# omicron2.net
KiCad netlist of a schematic drawn in EAGLE
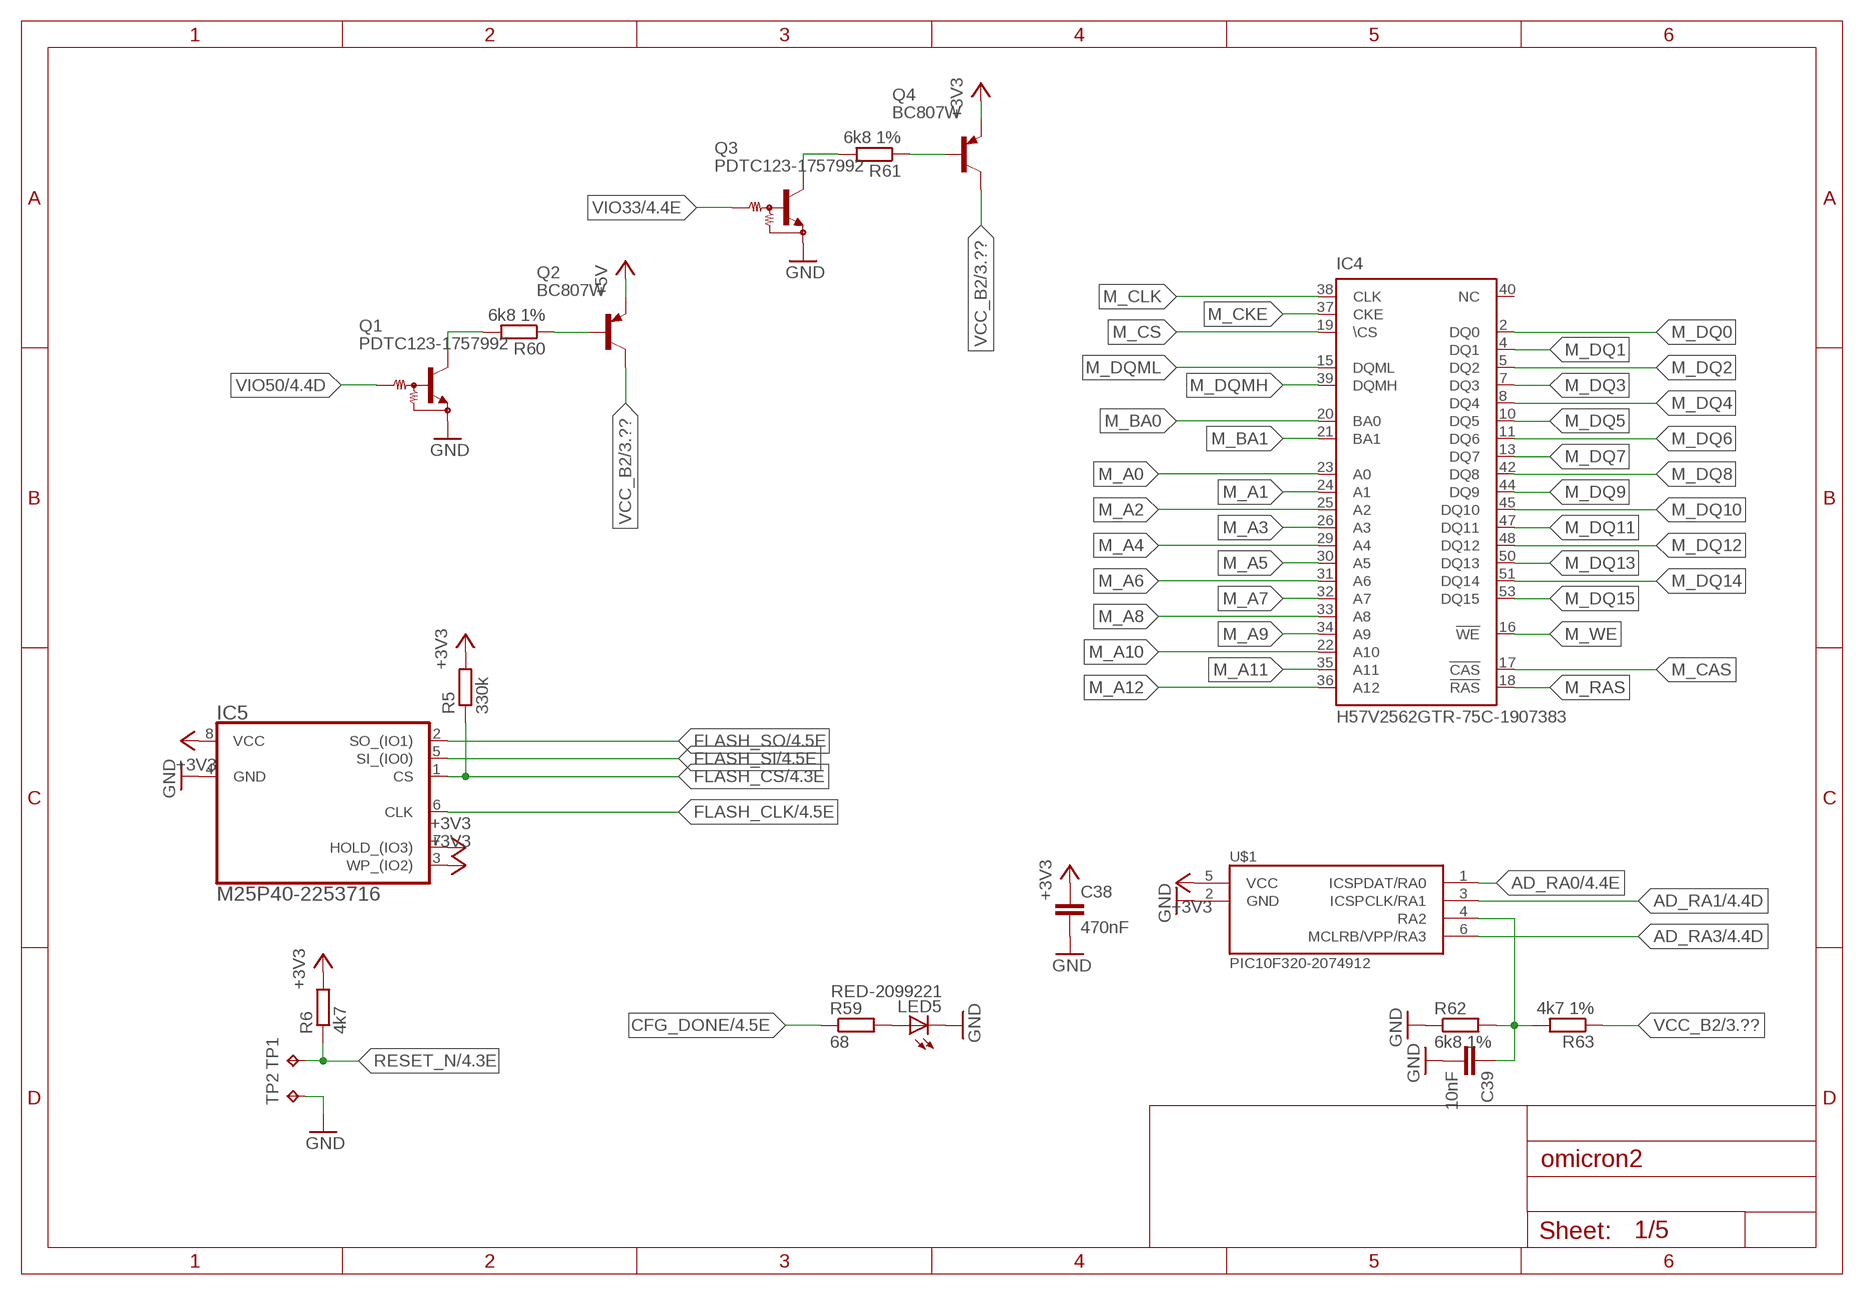
[diagram p0: schematic, sheet 1]
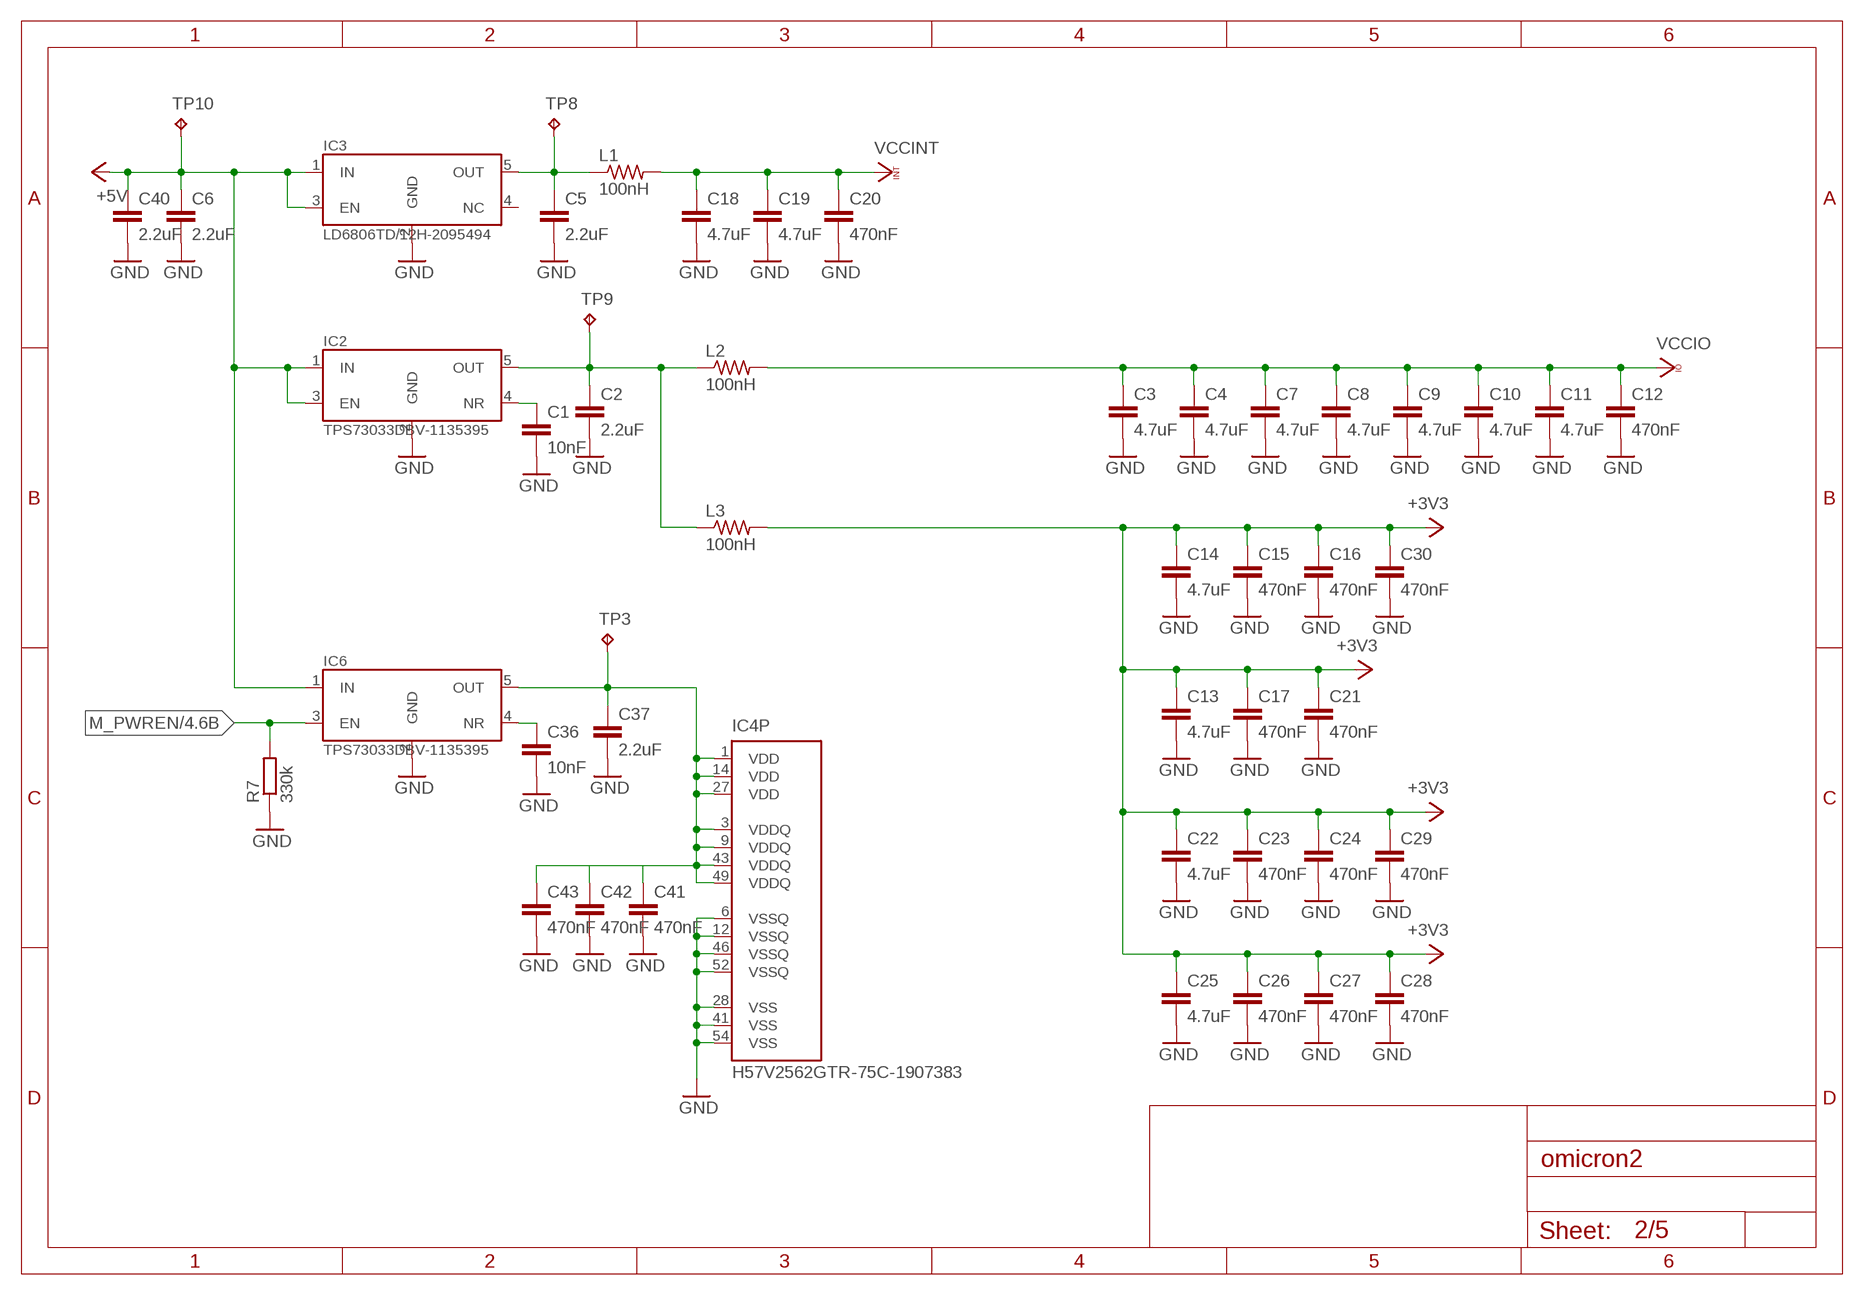
[diagram p1: schematic, sheet 2]
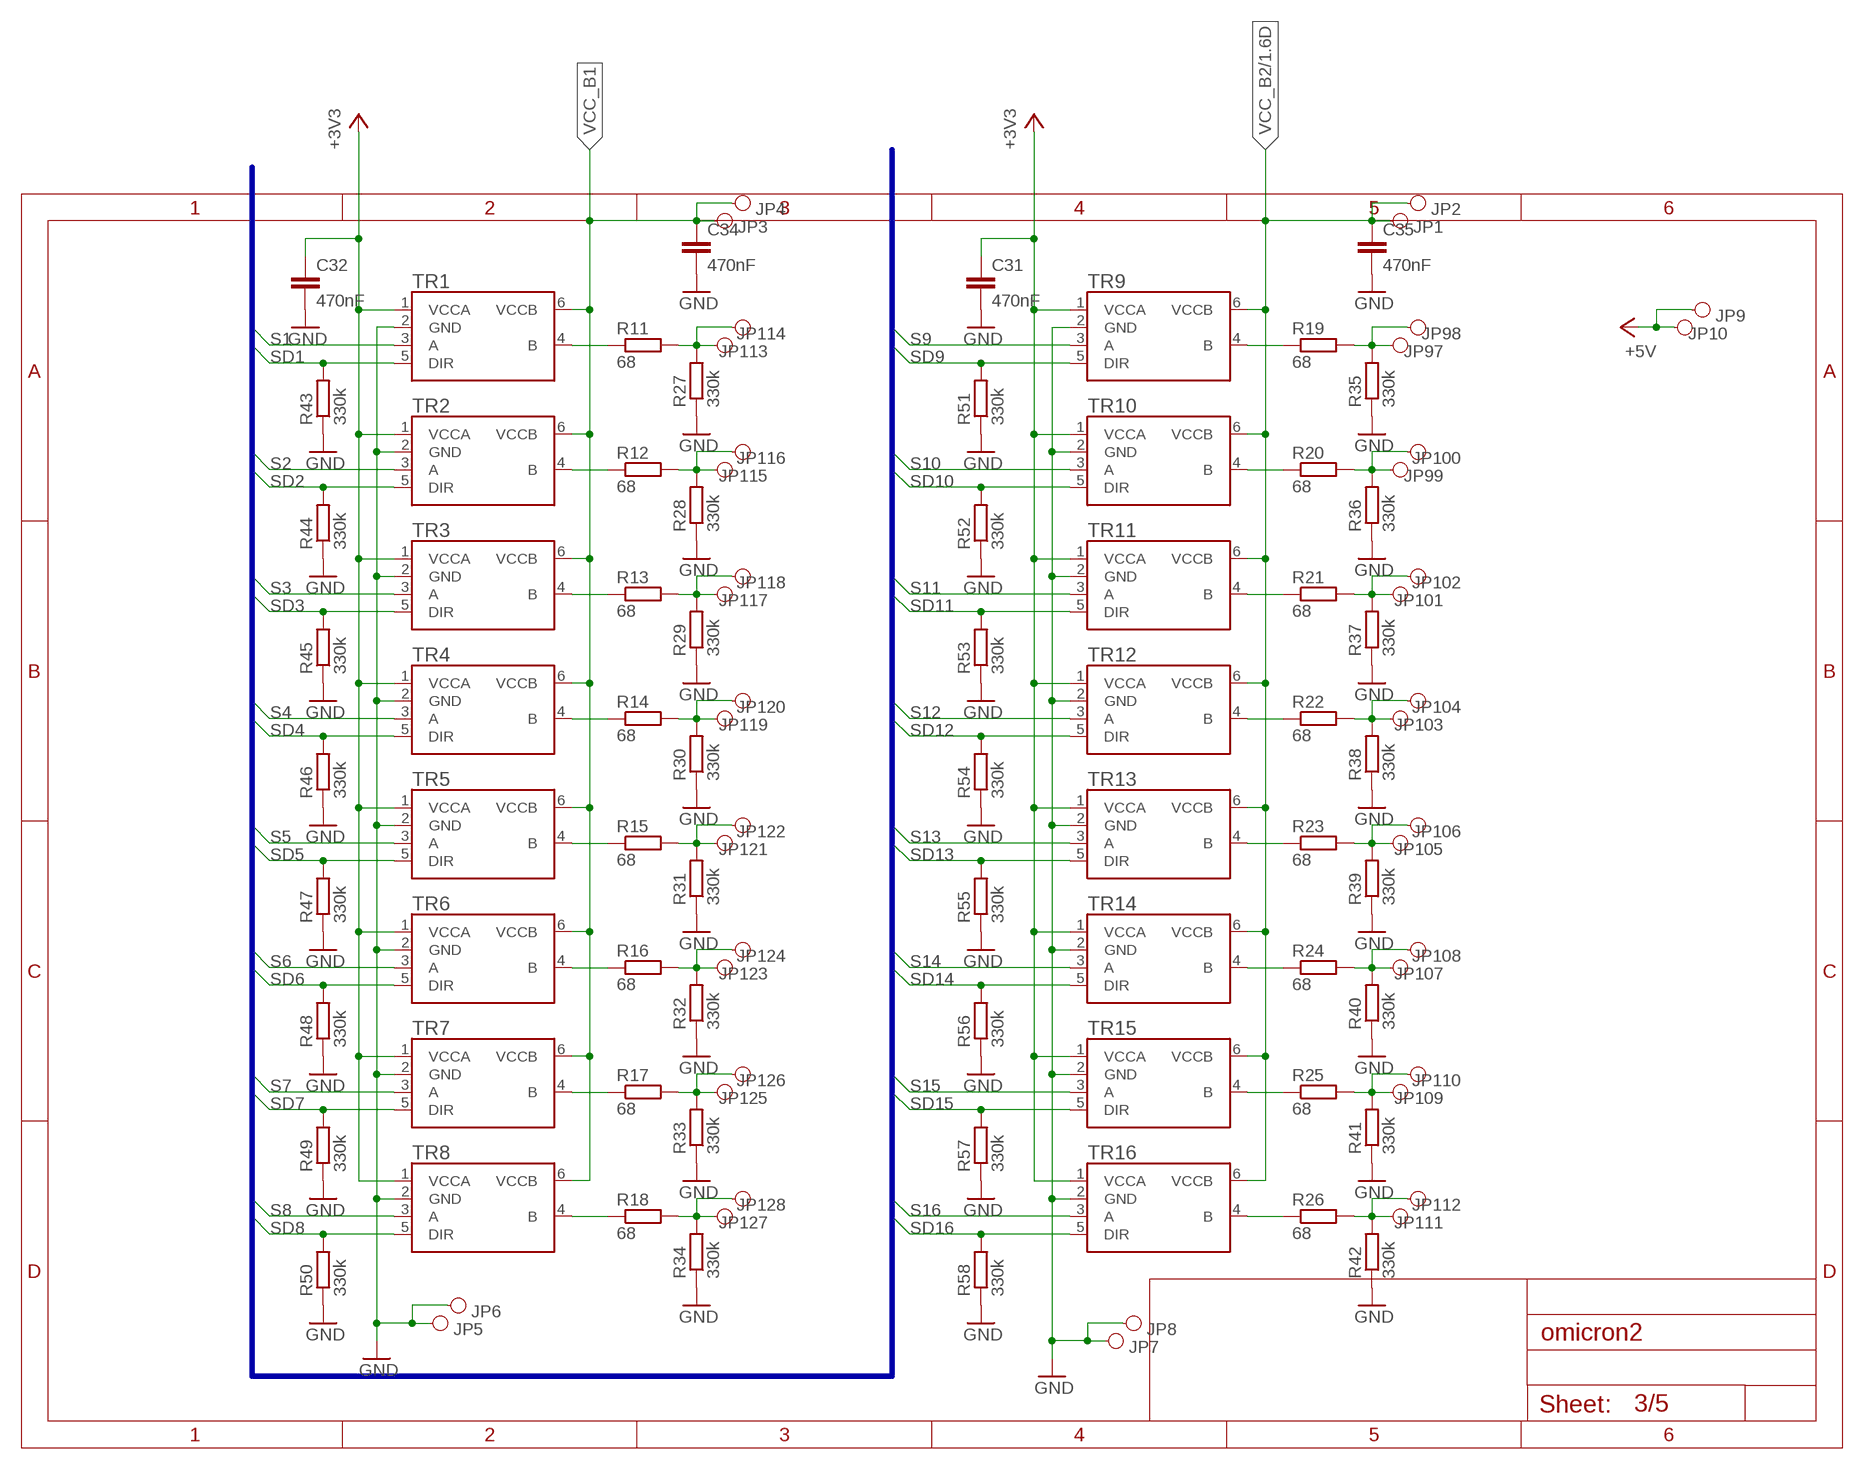
[diagram p2: schematic, sheet 3]
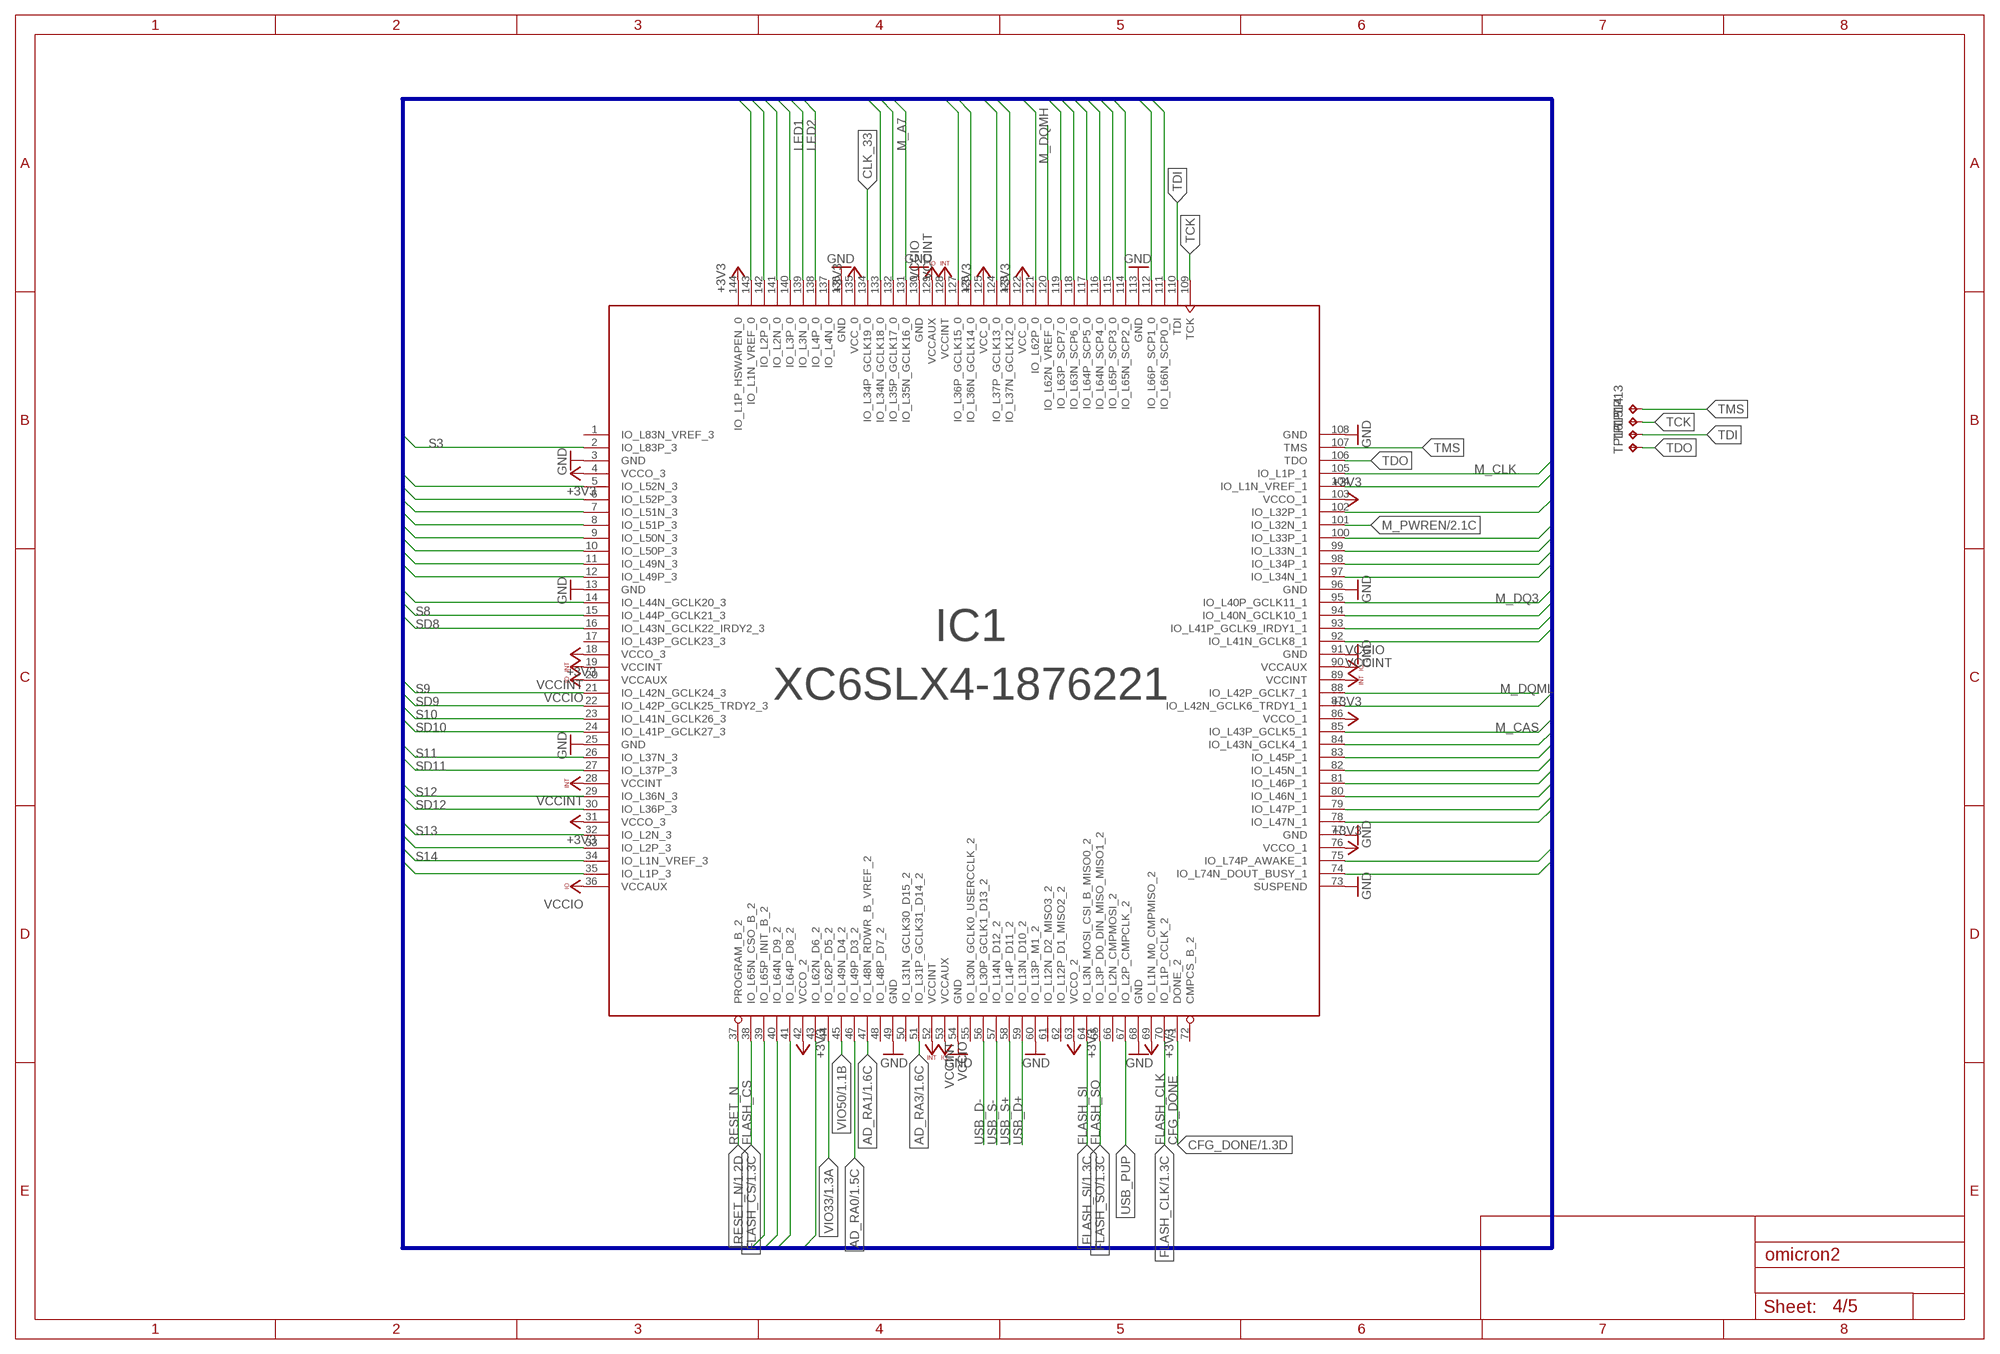
[diagram p3: schematic, sheet 4]
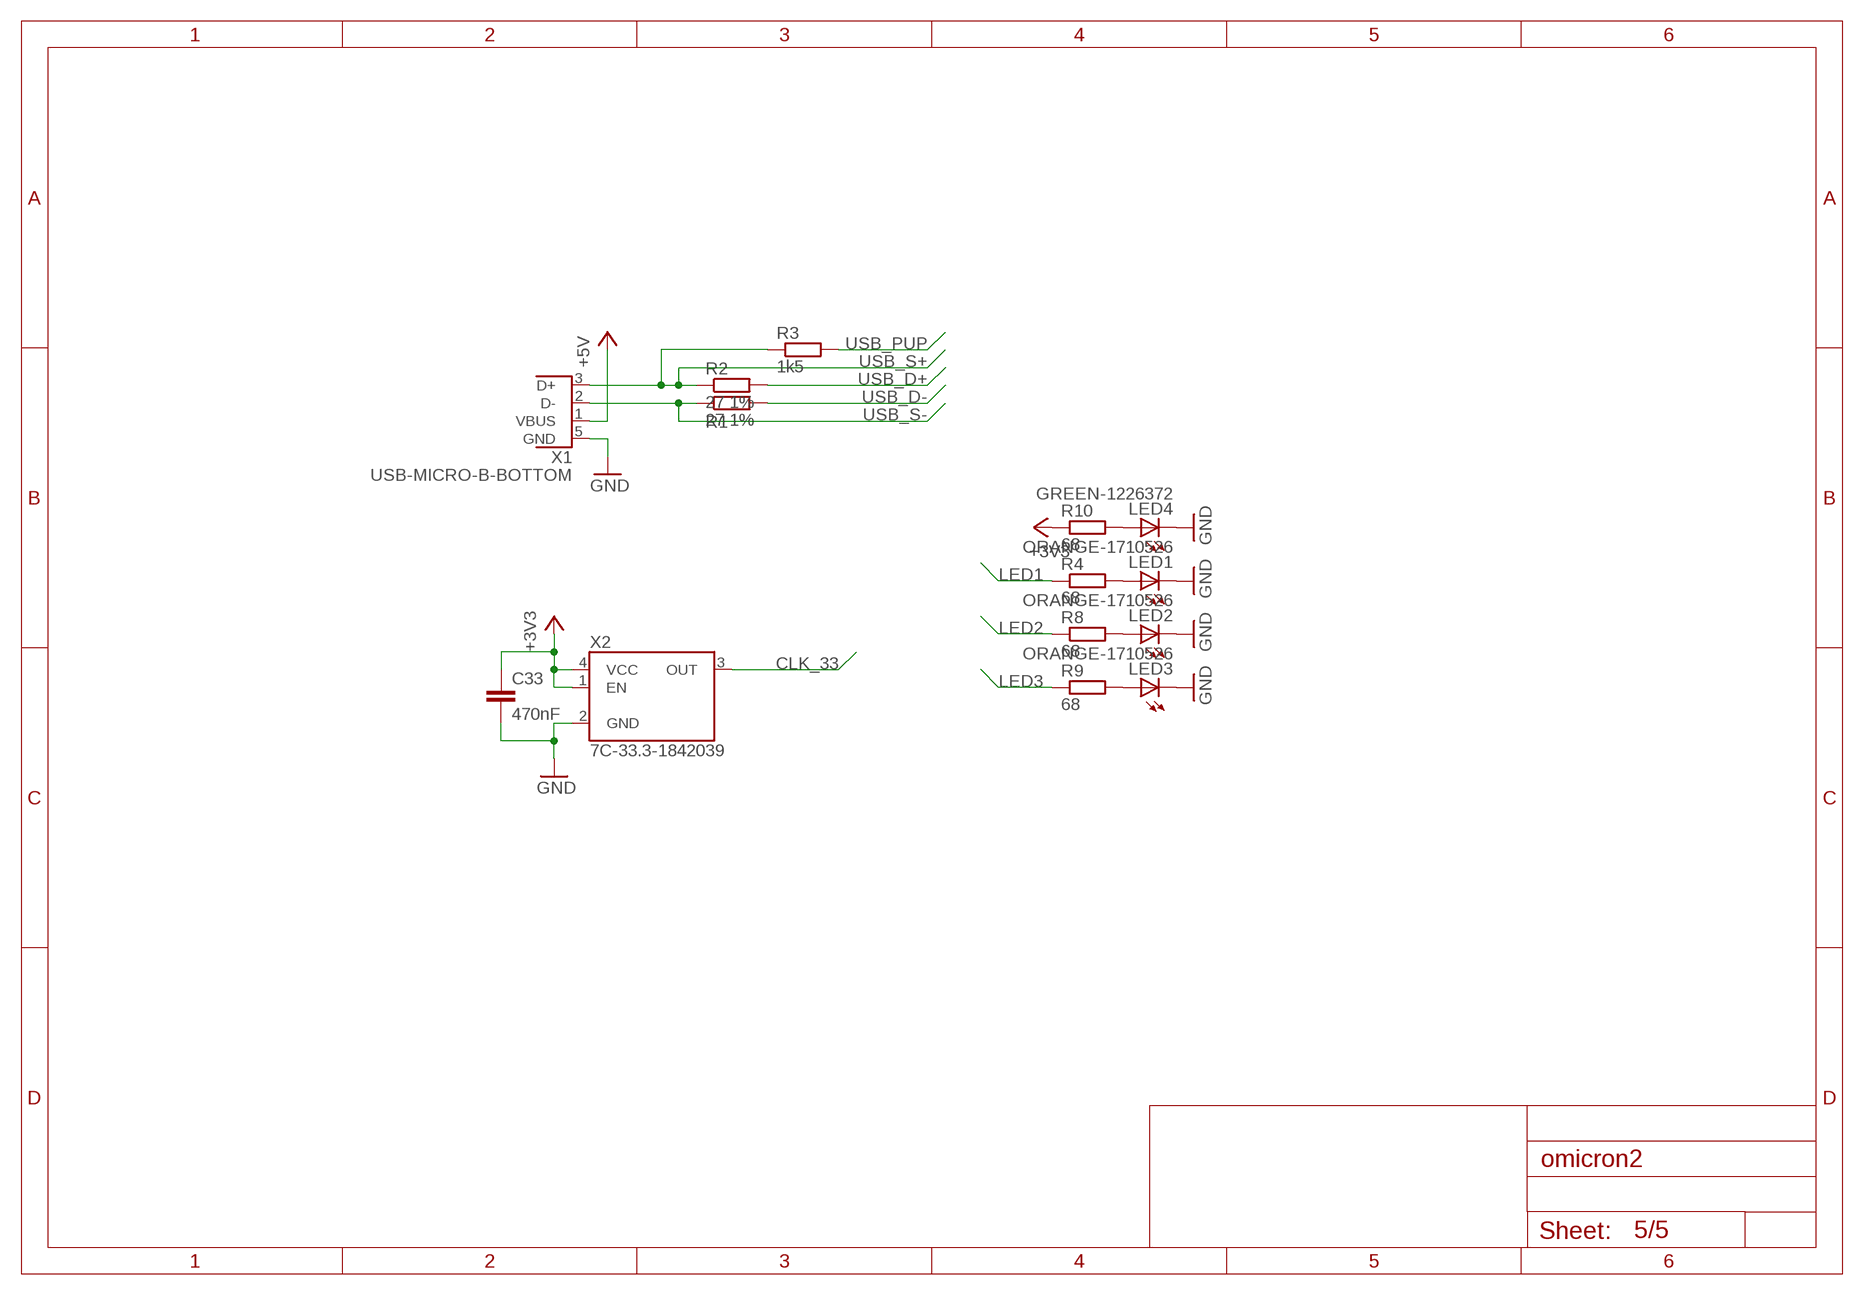
[diagram p4: schematic, sheet 5]

(export (version "E")
  (design (tool "Eeschema 10.0.6"))
  (components
    (comp (ref "C38")
      (value "470nF")
      (footprint "eagle-import:C0603")
      (libsource (lib "eagle-import") (part "C-EUC0603"))
    )
    (comp (ref "C39")
      (value "10nF")
      (footprint "eagle-import:C0603")
      (libsource (lib "eagle-import") (part "C-EUC0603"))
    )
    (comp (ref "IC4")
      (value "H57V2562GTR-75C-1907383")
      (footprint "eagle-import:TSOP54-400")
      (libsource (lib "eagle-import") (part "MT48LC64M4A2"))
    )
    (comp (ref "IC5")
      (value "M25P40-2253716")
      (footprint "eagle-import:SO8")
      (libsource (lib "eagle-import") (part "FLASH"))
    )
    (comp (ref "LED5")
      (value "RED-2099221")
      (footprint "eagle-import:CHIPLED_0603")
      (libsource (lib "eagle-import") (part "LEDCHIPLED_0603"))
    )
    (comp (ref "Q1")
      (value "PDTC123-1757992")
      (footprint "eagle-import:SOT323")
      (libsource (lib "eagle-import") (part "NPN-BIAS-SOT323-BEC"))
    )
    (comp (ref "Q2")
      (value "BC807W")
      (footprint "eagle-import:SOT323-BEC")
      (libsource (lib "eagle-import") (part "BC807W"))
    )
    (comp (ref "Q3")
      (value "PDTC123-1757992")
      (footprint "eagle-import:SOT323")
      (libsource (lib "eagle-import") (part "NPN-BIAS-SOT323-BEC"))
    )
    (comp (ref "Q4")
      (value "BC807W")
      (footprint "eagle-import:SOT323-BEC")
      (libsource (lib "eagle-import") (part "BC807W"))
    )
    (comp (ref "R5")
      (value "330k")
      (footprint "eagle-import:R0603")
      (libsource (lib "eagle-import") (part "R-EU_R0603"))
    )
    (comp (ref "R6")
      (value "4k7")
      (footprint "eagle-import:R0603")
      (libsource (lib "eagle-import") (part "R-EU_R0603"))
    )
    (comp (ref "R59")
      (value "68")
      (footprint "eagle-import:R0603")
      (libsource (lib "eagle-import") (part "R-EU_R0603"))
    )
    (comp (ref "R60")
      (value "6k8 1%")
      (footprint "eagle-import:R0603")
      (libsource (lib "eagle-import") (part "R-EU_R0603"))
    )
    (comp (ref "R61")
      (value "6k8 1%")
      (footprint "eagle-import:R0603")
      (libsource (lib "eagle-import") (part "R-EU_R0603"))
    )
    (comp (ref "R62")
      (value "6k8 1%")
      (footprint "eagle-import:R0603")
      (libsource (lib "eagle-import") (part "R-EU_R0603"))
    )
    (comp (ref "R63")
      (value "4k7 1%")
      (footprint "eagle-import:R0603")
      (libsource (lib "eagle-import") (part "R-EU_R0603"))
    )
    (comp (ref "TP1")
      (value "TPTP15R")
      (footprint "eagle-import:TP15R")
      (libsource (lib "eagle-import") (part "TPTP15R"))
    )
    (comp (ref "TP2")
      (value "TPTP20R")
      (footprint "eagle-import:TP20R")
      (libsource (lib "eagle-import") (part "TPTP20R"))
    )
    (comp (ref "U$1")
      (value "PIC10F320-2074912")
      (footprint "eagle-import:SOT23")
      (libsource (lib "eagle-import") (part "PIC10F320"))
    )
    (comp (ref "C33")
      (value "470nF")
      (footprint "eagle-import:C0603")
      (libsource (lib "eagle-import") (part "C-EUC0603"))
    )
    (comp (ref "LED1")
      (value "ORANGE-1710526")
      (footprint "eagle-import:CHIPLED_0603")
      (libsource (lib "eagle-import") (part "LEDCHIPLED_0603"))
    )
    (comp (ref "LED2")
      (value "ORANGE-1710526")
      (footprint "eagle-import:CHIPLED_0603")
      (libsource (lib "eagle-import") (part "LEDCHIPLED_0603"))
    )
    (comp (ref "LED3")
      (value "ORANGE-1710526")
      (footprint "eagle-import:CHIPLED_0603")
      (libsource (lib "eagle-import") (part "LEDCHIPLED_0603"))
    )
    (comp (ref "LED4")
      (value "GREEN-1226372")
      (footprint "eagle-import:CHIPLED_0603")
      (libsource (lib "eagle-import") (part "LEDCHIPLED_0603"))
    )
    (comp (ref "R1")
      (value "27 1%")
      (footprint "eagle-import:R0603")
      (libsource (lib "eagle-import") (part "R-EU_R0603"))
    )
    (comp (ref "R2")
      (value "27 1%")
      (footprint "eagle-import:R0603")
      (libsource (lib "eagle-import") (part "R-EU_R0603"))
    )
    (comp (ref "R3")
      (value "1k5")
      (footprint "eagle-import:R0603")
      (libsource (lib "eagle-import") (part "R-EU_R0603"))
    )
    (comp (ref "R4")
      (value "68")
      (footprint "eagle-import:R0603")
      (libsource (lib "eagle-import") (part "R-EU_R0603"))
    )
    (comp (ref "R8")
      (value "68")
      (footprint "eagle-import:R0603")
      (libsource (lib "eagle-import") (part "R-EU_R0603"))
    )
    (comp (ref "R9")
      (value "68")
      (footprint "eagle-import:R0603")
      (libsource (lib "eagle-import") (part "R-EU_R0603"))
    )
    (comp (ref "R10")
      (value "68")
      (footprint "eagle-import:R0603")
      (libsource (lib "eagle-import") (part "R-EU_R0603"))
    )
    (comp (ref "X1")
      (value "USB-MICRO-B-BOTTOM")
      (footprint "eagle-import:USB-MICRO-B-BOTTOM-MOLEX")
      (libsource (lib "eagle-import") (part "USB-MICRO-B-BOTTOM"))
    )
    (comp (ref "X2")
      (value "7C-33.3-1842039")
      (footprint "eagle-import:5X3.2_HAND")
      (libsource (lib "eagle-import") (part "OSC-5X3.2HS"))
    )
    (comp (ref "C31")
      (value "470nF")
      (footprint "eagle-import:C0603")
      (libsource (lib "eagle-import") (part "C-EUC0603"))
    )
    (comp (ref "C32")
      (value "470nF")
      (footprint "eagle-import:C0603")
      (libsource (lib "eagle-import") (part "C-EUC0603"))
    )
    (comp (ref "C34")
      (value "470nF")
      (footprint "eagle-import:C0603")
      (libsource (lib "eagle-import") (part "C-EUC0603"))
    )
    (comp (ref "C35")
      (value "470nF")
      (footprint "eagle-import:C0603")
      (libsource (lib "eagle-import") (part "C-EUC0603"))
    )
    (comp (ref "JP1")
      (value "PINH1X01SMD")
      (footprint "eagle-import:PINH1X01SMD")
      (libsource (lib "eagle-import") (part "PINH1X01SMD"))
    )
    (comp (ref "JP2")
      (value "PINH1X01SMD")
      (footprint "eagle-import:PINH1X01SMD")
      (libsource (lib "eagle-import") (part "PINH1X01SMD"))
    )
    (comp (ref "JP3")
      (value "PINH1X01SMD")
      (footprint "eagle-import:PINH1X01SMD")
      (libsource (lib "eagle-import") (part "PINH1X01SMD"))
    )
    (comp (ref "JP4")
      (value "PINH1X01SMD")
      (footprint "eagle-import:PINH1X01SMD")
      (libsource (lib "eagle-import") (part "PINH1X01SMD"))
    )
    (comp (ref "JP5")
      (value "PINH1X01SMD")
      (footprint "eagle-import:PINH1X01SMD")
      (libsource (lib "eagle-import") (part "PINH1X01SMD"))
    )
    (comp (ref "JP6")
      (value "PINH1X01SMD")
      (footprint "eagle-import:PINH1X01SMD")
      (libsource (lib "eagle-import") (part "PINH1X01SMD"))
    )
    (comp (ref "JP7")
      (value "PINH1X01SMD")
      (footprint "eagle-import:PINH1X01SMD")
      (libsource (lib "eagle-import") (part "PINH1X01SMD"))
    )
    (comp (ref "JP8")
      (value "PINH1X01SMD")
      (footprint "eagle-import:PINH1X01SMD")
      (libsource (lib "eagle-import") (part "PINH1X01SMD"))
    )
    (comp (ref "JP9")
      (value "PINH1X01SMD")
      (footprint "eagle-import:PINH1X01SMD")
      (libsource (lib "eagle-import") (part "PINH1X01SMD"))
    )
    (comp (ref "JP10")
      (value "PINH1X01SMD")
      (footprint "eagle-import:PINH1X01SMD")
      (libsource (lib "eagle-import") (part "PINH1X01SMD"))
    )
    (comp (ref "JP97")
      (value "PINH1X01SMD")
      (footprint "eagle-import:PINH1X01SMD")
      (libsource (lib "eagle-import") (part "PINH1X01SMD"))
    )
    (comp (ref "JP98")
      (value "PINH1X01SMD")
      (footprint "eagle-import:PINH1X01SMD")
      (libsource (lib "eagle-import") (part "PINH1X01SMD"))
    )
    (comp (ref "JP99")
      (value "PINH1X01SMD")
      (footprint "eagle-import:PINH1X01SMD")
      (libsource (lib "eagle-import") (part "PINH1X01SMD"))
    )
    (comp (ref "JP100")
      (value "PINH1X01SMD")
      (footprint "eagle-import:PINH1X01SMD")
      (libsource (lib "eagle-import") (part "PINH1X01SMD"))
    )
    (comp (ref "JP101")
      (value "PINH1X01SMD")
      (footprint "eagle-import:PINH1X01SMD")
      (libsource (lib "eagle-import") (part "PINH1X01SMD"))
    )
    (comp (ref "JP102")
      (value "PINH1X01SMD")
      (footprint "eagle-import:PINH1X01SMD")
      (libsource (lib "eagle-import") (part "PINH1X01SMD"))
    )
    (comp (ref "JP103")
      (value "PINH1X01SMD")
      (footprint "eagle-import:PINH1X01SMD")
      (libsource (lib "eagle-import") (part "PINH1X01SMD"))
    )
    (comp (ref "JP104")
      (value "PINH1X01SMD")
      (footprint "eagle-import:PINH1X01SMD")
      (libsource (lib "eagle-import") (part "PINH1X01SMD"))
    )
    (comp (ref "JP105")
      (value "PINH1X01SMD")
      (footprint "eagle-import:PINH1X01SMD")
      (libsource (lib "eagle-import") (part "PINH1X01SMD"))
    )
    (comp (ref "JP106")
      (value "PINH1X01SMD")
      (footprint "eagle-import:PINH1X01SMD")
      (libsource (lib "eagle-import") (part "PINH1X01SMD"))
    )
    (comp (ref "JP107")
      (value "PINH1X01SMD")
      (footprint "eagle-import:PINH1X01SMD")
      (libsource (lib "eagle-import") (part "PINH1X01SMD"))
    )
    (comp (ref "JP108")
      (value "PINH1X01SMD")
      (footprint "eagle-import:PINH1X01SMD")
      (libsource (lib "eagle-import") (part "PINH1X01SMD"))
    )
    (comp (ref "JP109")
      (value "PINH1X01SMD")
      (footprint "eagle-import:PINH1X01SMD")
      (libsource (lib "eagle-import") (part "PINH1X01SMD"))
    )
    (comp (ref "JP110")
      (value "PINH1X01SMD")
      (footprint "eagle-import:PINH1X01SMD")
      (libsource (lib "eagle-import") (part "PINH1X01SMD"))
    )
    (comp (ref "JP111")
      (value "PINH1X01SMD")
      (footprint "eagle-import:PINH1X01SMD")
      (libsource (lib "eagle-import") (part "PINH1X01SMD"))
    )
    (comp (ref "JP112")
      (value "PINH1X01SMD")
      (footprint "eagle-import:PINH1X01SMD")
      (libsource (lib "eagle-import") (part "PINH1X01SMD"))
    )
    (comp (ref "JP113")
      (value "PINH1X01SMD")
      (footprint "eagle-import:PINH1X01SMD")
      (libsource (lib "eagle-import") (part "PINH1X01SMD"))
    )
    (comp (ref "JP114")
      (value "PINH1X01SMD")
      (footprint "eagle-import:PINH1X01SMD")
      (libsource (lib "eagle-import") (part "PINH1X01SMD"))
    )
    (comp (ref "JP115")
      (value "PINH1X01SMD")
      (footprint "eagle-import:PINH1X01SMD")
      (libsource (lib "eagle-import") (part "PINH1X01SMD"))
    )
    (comp (ref "JP116")
      (value "PINH1X01SMD")
      (footprint "eagle-import:PINH1X01SMD")
      (libsource (lib "eagle-import") (part "PINH1X01SMD"))
    )
    (comp (ref "JP117")
      (value "PINH1X01SMD")
      (footprint "eagle-import:PINH1X01SMD")
      (libsource (lib "eagle-import") (part "PINH1X01SMD"))
    )
    (comp (ref "JP118")
      (value "PINH1X01SMD")
      (footprint "eagle-import:PINH1X01SMD")
      (libsource (lib "eagle-import") (part "PINH1X01SMD"))
    )
    (comp (ref "JP119")
      (value "PINH1X01SMD")
      (footprint "eagle-import:PINH1X01SMD")
      (libsource (lib "eagle-import") (part "PINH1X01SMD"))
    )
    (comp (ref "JP120")
      (value "PINH1X01SMD")
      (footprint "eagle-import:PINH1X01SMD")
      (libsource (lib "eagle-import") (part "PINH1X01SMD"))
    )
    (comp (ref "JP121")
      (value "PINH1X01SMD")
      (footprint "eagle-import:PINH1X01SMD")
      (libsource (lib "eagle-import") (part "PINH1X01SMD"))
    )
    (comp (ref "JP122")
      (value "PINH1X01SMD")
      (footprint "eagle-import:PINH1X01SMD")
      (libsource (lib "eagle-import") (part "PINH1X01SMD"))
    )
    (comp (ref "JP123")
      (value "PINH1X01SMD")
      (footprint "eagle-import:PINH1X01SMD")
      (libsource (lib "eagle-import") (part "PINH1X01SMD"))
    )
    (comp (ref "JP124")
      (value "PINH1X01SMD")
      (footprint "eagle-import:PINH1X01SMD")
      (libsource (lib "eagle-import") (part "PINH1X01SMD"))
    )
    (comp (ref "JP125")
      (value "PINH1X01SMD")
      (footprint "eagle-import:PINH1X01SMD")
      (libsource (lib "eagle-import") (part "PINH1X01SMD"))
    )
    (comp (ref "JP126")
      (value "PINH1X01SMD")
      (footprint "eagle-import:PINH1X01SMD")
      (libsource (lib "eagle-import") (part "PINH1X01SMD"))
    )
    (comp (ref "JP127")
      (value "PINH1X01SMD")
      (footprint "eagle-import:PINH1X01SMD")
      (libsource (lib "eagle-import") (part "PINH1X01SMD"))
    )
    (comp (ref "JP128")
      (value "PINH1X01SMD")
      (footprint "eagle-import:PINH1X01SMD")
      (libsource (lib "eagle-import") (part "PINH1X01SMD"))
    )
    (comp (ref "R11")
      (value "68")
      (footprint "eagle-import:R0603")
      (libsource (lib "eagle-import") (part "R-EU_R0603"))
    )
    (comp (ref "R12")
      (value "68")
      (footprint "eagle-import:R0603")
      (libsource (lib "eagle-import") (part "R-EU_R0603"))
    )
    (comp (ref "R13")
      (value "68")
      (footprint "eagle-import:R0603")
      (libsource (lib "eagle-import") (part "R-EU_R0603"))
    )
    (comp (ref "R14")
      (value "68")
      (footprint "eagle-import:R0603")
      (libsource (lib "eagle-import") (part "R-EU_R0603"))
    )
    (comp (ref "R15")
      (value "68")
      (footprint "eagle-import:R0603")
      (libsource (lib "eagle-import") (part "R-EU_R0603"))
    )
    (comp (ref "R16")
      (value "68")
      (footprint "eagle-import:R0603")
      (libsource (lib "eagle-import") (part "R-EU_R0603"))
    )
    (comp (ref "R17")
      (value "68")
      (footprint "eagle-import:R0603")
      (libsource (lib "eagle-import") (part "R-EU_R0603"))
    )
    (comp (ref "R18")
      (value "68")
      (footprint "eagle-import:R0603")
      (libsource (lib "eagle-import") (part "R-EU_R0603"))
    )
    (comp (ref "R19")
      (value "68")
      (footprint "eagle-import:R0603")
      (libsource (lib "eagle-import") (part "R-EU_R0603"))
    )
    (comp (ref "R20")
      (value "68")
      (footprint "eagle-import:R0603")
      (libsource (lib "eagle-import") (part "R-EU_R0603"))
    )
    (comp (ref "R21")
      (value "68")
      (footprint "eagle-import:R0603")
      (libsource (lib "eagle-import") (part "R-EU_R0603"))
    )
    (comp (ref "R22")
      (value "68")
      (footprint "eagle-import:R0603")
      (libsource (lib "eagle-import") (part "R-EU_R0603"))
    )
    (comp (ref "R23")
      (value "68")
      (footprint "eagle-import:R0603")
      (libsource (lib "eagle-import") (part "R-EU_R0603"))
    )
    (comp (ref "R24")
      (value "68")
      (footprint "eagle-import:R0603")
      (libsource (lib "eagle-import") (part "R-EU_R0603"))
    )
    (comp (ref "R25")
      (value "68")
      (footprint "eagle-import:R0603")
      (libsource (lib "eagle-import") (part "R-EU_R0603"))
    )
    (comp (ref "R26")
      (value "68")
      (footprint "eagle-import:R0603")
      (libsource (lib "eagle-import") (part "R-EU_R0603"))
    )
    (comp (ref "R27")
      (value "330k")
      (footprint "eagle-import:R0603")
      (libsource (lib "eagle-import") (part "R-EU_R0603"))
    )
    (comp (ref "R28")
      (value "330k")
      (footprint "eagle-import:R0603")
      (libsource (lib "eagle-import") (part "R-EU_R0603"))
    )
    (comp (ref "R29")
      (value "330k")
      (footprint "eagle-import:R0603")
      (libsource (lib "eagle-import") (part "R-EU_R0603"))
    )
    (comp (ref "R30")
      (value "330k")
      (footprint "eagle-import:R0603")
      (libsource (lib "eagle-import") (part "R-EU_R0603"))
    )
    (comp (ref "R31")
      (value "330k")
      (footprint "eagle-import:R0603")
      (libsource (lib "eagle-import") (part "R-EU_R0603"))
    )
    (comp (ref "R32")
      (value "330k")
      (footprint "eagle-import:R0603")
      (libsource (lib "eagle-import") (part "R-EU_R0603"))
    )
    (comp (ref "R33")
      (value "330k")
      (footprint "eagle-import:R0603")
      (libsource (lib "eagle-import") (part "R-EU_R0603"))
    )
    (comp (ref "R34")
      (value "330k")
      (footprint "eagle-import:R0603")
      (libsource (lib "eagle-import") (part "R-EU_R0603"))
    )
    (comp (ref "R35")
      (value "330k")
      (footprint "eagle-import:R0603")
      (libsource (lib "eagle-import") (part "R-EU_R0603"))
    )
    (comp (ref "R36")
      (value "330k")
      (footprint "eagle-import:R0603")
      (libsource (lib "eagle-import") (part "R-EU_R0603"))
    )
    (comp (ref "R37")
      (value "330k")
      (footprint "eagle-import:R0603")
      (libsource (lib "eagle-import") (part "R-EU_R0603"))
    )
    (comp (ref "R38")
      (value "330k")
      (footprint "eagle-import:R0603")
      (libsource (lib "eagle-import") (part "R-EU_R0603"))
    )
    (comp (ref "R39")
      (value "330k")
      (footprint "eagle-import:R0603")
      (libsource (lib "eagle-import") (part "R-EU_R0603"))
    )
    (comp (ref "R40")
      (value "330k")
      (footprint "eagle-import:R0603")
      (libsource (lib "eagle-import") (part "R-EU_R0603"))
    )
    (comp (ref "R41")
      (value "330k")
      (footprint "eagle-import:R0603")
      (libsource (lib "eagle-import") (part "R-EU_R0603"))
    )
    (comp (ref "R42")
      (value "330k")
      (footprint "eagle-import:R0603")
      (libsource (lib "eagle-import") (part "R-EU_R0603"))
    )
    (comp (ref "R43")
      (value "330k")
      (footprint "eagle-import:R0603")
      (libsource (lib "eagle-import") (part "R-EU_R0603"))
    )
    (comp (ref "R44")
      (value "330k")
      (footprint "eagle-import:R0603")
      (libsource (lib "eagle-import") (part "R-EU_R0603"))
    )
    (comp (ref "R45")
      (value "330k")
      (footprint "eagle-import:R0603")
      (libsource (lib "eagle-import") (part "R-EU_R0603"))
    )
    (comp (ref "R46")
      (value "330k")
      (footprint "eagle-import:R0603")
      (libsource (lib "eagle-import") (part "R-EU_R0603"))
    )
    (comp (ref "R47")
      (value "330k")
      (footprint "eagle-import:R0603")
      (libsource (lib "eagle-import") (part "R-EU_R0603"))
    )
    (comp (ref "R48")
      (value "330k")
      (footprint "eagle-import:R0603")
      (libsource (lib "eagle-import") (part "R-EU_R0603"))
    )
    (comp (ref "R49")
      (value "330k")
      (footprint "eagle-import:R0603")
      (libsource (lib "eagle-import") (part "R-EU_R0603"))
    )
    (comp (ref "R50")
      (value "330k")
      (footprint "eagle-import:R0603")
      (libsource (lib "eagle-import") (part "R-EU_R0603"))
    )
    (comp (ref "R51")
      (value "330k")
      (footprint "eagle-import:R0603")
      (libsource (lib "eagle-import") (part "R-EU_R0603"))
    )
    (comp (ref "R52")
      (value "330k")
      (footprint "eagle-import:R0603")
      (libsource (lib "eagle-import") (part "R-EU_R0603"))
    )
    (comp (ref "R53")
      (value "330k")
      (footprint "eagle-import:R0603")
      (libsource (lib "eagle-import") (part "R-EU_R0603"))
    )
    (comp (ref "R54")
      (value "330k")
      (footprint "eagle-import:R0603")
      (libsource (lib "eagle-import") (part "R-EU_R0603"))
    )
    (comp (ref "R55")
      (value "330k")
      (footprint "eagle-import:R0603")
      (libsource (lib "eagle-import") (part "R-EU_R0603"))
    )
    (comp (ref "R56")
      (value "330k")
      (footprint "eagle-import:R0603")
      (libsource (lib "eagle-import") (part "R-EU_R0603"))
    )
    (comp (ref "R57")
      (value "330k")
      (footprint "eagle-import:R0603")
      (libsource (lib "eagle-import") (part "R-EU_R0603"))
    )
    (comp (ref "R58")
      (value "330k")
      (footprint "eagle-import:R0603")
      (libsource (lib "eagle-import") (part "R-EU_R0603"))
    )
    (comp (ref "TR1")
      (value "74LVC1T45DBV")
      (footprint "eagle-import:SOT236")
      (libsource (lib "eagle-import") (part "741T45DBVLVC"))
    )
    (comp (ref "TR2")
      (value "74LVC1T45DBV")
      (footprint "eagle-import:SOT236")
      (libsource (lib "eagle-import") (part "741T45DBVLVC"))
    )
    (comp (ref "TR3")
      (value "74LVC1T45DBV")
      (footprint "eagle-import:SOT236")
      (libsource (lib "eagle-import") (part "741T45DBVLVC"))
    )
    (comp (ref "TR4")
      (value "74LVC1T45DBV")
      (footprint "eagle-import:SOT236")
      (libsource (lib "eagle-import") (part "741T45DBVLVC"))
    )
    (comp (ref "TR5")
      (value "74LVC1T45DBV")
      (footprint "eagle-import:SOT236")
      (libsource (lib "eagle-import") (part "741T45DBVLVC"))
    )
    (comp (ref "TR6")
      (value "74LVC1T45DBV")
      (footprint "eagle-import:SOT236")
      (libsource (lib "eagle-import") (part "741T45DBVLVC"))
    )
    (comp (ref "TR7")
      (value "74LVC1T45DBV")
      (footprint "eagle-import:SOT236")
      (libsource (lib "eagle-import") (part "741T45DBVLVC"))
    )
    (comp (ref "TR8")
      (value "74LVC1T45DBV")
      (footprint "eagle-import:SOT236")
      (libsource (lib "eagle-import") (part "741T45DBVLVC"))
    )
    (comp (ref "TR9")
      (value "74LVC1T45DBV")
      (footprint "eagle-import:SOT236")
      (libsource (lib "eagle-import") (part "741T45DBVLVC"))
    )
    (comp (ref "TR10")
      (value "74LVC1T45DBV")
      (footprint "eagle-import:SOT236")
      (libsource (lib "eagle-import") (part "741T45DBVLVC"))
    )
    (comp (ref "TR11")
      (value "74LVC1T45DBV")
      (footprint "eagle-import:SOT236")
      (libsource (lib "eagle-import") (part "741T45DBVLVC"))
    )
    (comp (ref "TR12")
      (value "74LVC1T45DBV")
      (footprint "eagle-import:SOT236")
      (libsource (lib "eagle-import") (part "741T45DBVLVC"))
    )
    (comp (ref "TR13")
      (value "74LVC1T45DBV")
      (footprint "eagle-import:SOT236")
      (libsource (lib "eagle-import") (part "741T45DBVLVC"))
    )
    (comp (ref "TR14")
      (value "74LVC1T45DBV")
      (footprint "eagle-import:SOT236")
      (libsource (lib "eagle-import") (part "741T45DBVLVC"))
    )
    (comp (ref "TR15")
      (value "74LVC1T45DBV")
      (footprint "eagle-import:SOT236")
      (libsource (lib "eagle-import") (part "741T45DBVLVC"))
    )
    (comp (ref "TR16")
      (value "74LVC1T45DBV")
      (footprint "eagle-import:SOT236")
      (libsource (lib "eagle-import") (part "741T45DBVLVC"))
    )
    (comp (ref "IC1")
      (value "XC6SLX4-1876221")
      (footprint "eagle-import:TQG144")
      (libsource (lib "eagle-import") (part "XC6SLX4TQG144-2"))
    )
    (comp (ref "TP13")
      (value "TPTP20R")
      (footprint "eagle-import:TP20R")
      (libsource (lib "eagle-import") (part "TPTP20R"))
    )
    (comp (ref "TP14")
      (value "TPTP20R")
      (footprint "eagle-import:TP20R")
      (libsource (lib "eagle-import") (part "TPTP20R"))
    )
    (comp (ref "TP15")
      (value "TPTP20R")
      (footprint "eagle-import:TP20R")
      (libsource (lib "eagle-import") (part "TPTP20R"))
    )
    (comp (ref "TP16")
      (value "TPTP20R")
      (footprint "eagle-import:TP20R")
      (libsource (lib "eagle-import") (part "TPTP20R"))
    )
    (comp (ref "C1")
      (value "10nF")
      (footprint "eagle-import:C0603")
      (libsource (lib "eagle-import") (part "C-EUC0603"))
    )
    (comp (ref "C2")
      (value "2.2uF")
      (footprint "eagle-import:C0603")
      (libsource (lib "eagle-import") (part "C-EUC0603"))
    )
    (comp (ref "C3")
      (value "4.7uF")
      (footprint "eagle-import:C0603")
      (libsource (lib "eagle-import") (part "C-EUC0603"))
    )
    (comp (ref "C4")
      (value "4.7uF")
      (footprint "eagle-import:C0603")
      (libsource (lib "eagle-import") (part "C-EUC0603"))
    )
    (comp (ref "C5")
      (value "2.2uF")
      (footprint "eagle-import:C0603")
      (libsource (lib "eagle-import") (part "C-EUC0603"))
    )
    (comp (ref "C6")
      (value "2.2uF")
      (footprint "eagle-import:C0603")
      (libsource (lib "eagle-import") (part "C-EUC0603"))
    )
    (comp (ref "C7")
      (value "4.7uF")
      (footprint "eagle-import:C0603")
      (libsource (lib "eagle-import") (part "C-EUC0603"))
    )
    (comp (ref "C8")
      (value "4.7uF")
      (footprint "eagle-import:C0603")
      (libsource (lib "eagle-import") (part "C-EUC0603"))
    )
    (comp (ref "C9")
      (value "4.7uF")
      (footprint "eagle-import:C0603")
      (libsource (lib "eagle-import") (part "C-EUC0603"))
    )
    (comp (ref "C10")
      (value "4.7uF")
      (footprint "eagle-import:C0603")
      (libsource (lib "eagle-import") (part "C-EUC0603"))
    )
    (comp (ref "C11")
      (value "4.7uF")
      (footprint "eagle-import:C0603")
      (libsource (lib "eagle-import") (part "C-EUC0603"))
    )
    (comp (ref "C12")
      (value "470nF")
      (footprint "eagle-import:C0603")
      (libsource (lib "eagle-import") (part "C-EUC0603"))
    )
    (comp (ref "C13")
      (value "4.7uF")
      (footprint "eagle-import:C0603")
      (libsource (lib "eagle-import") (part "C-EUC0603"))
    )
    (comp (ref "C14")
      (value "4.7uF")
      (footprint "eagle-import:C0603")
      (libsource (lib "eagle-import") (part "C-EUC0603"))
    )
    (comp (ref "C15")
      (value "470nF")
      (footprint "eagle-import:C0603")
      (libsource (lib "eagle-import") (part "C-EUC0603"))
    )
    (comp (ref "C16")
      (value "470nF")
      (footprint "eagle-import:C0603")
      (libsource (lib "eagle-import") (part "C-EUC0603"))
    )
    (comp (ref "C17")
      (value "470nF")
      (footprint "eagle-import:C0603")
      (libsource (lib "eagle-import") (part "C-EUC0603"))
    )
    (comp (ref "C18")
      (value "4.7uF")
      (footprint "eagle-import:C0603")
      (libsource (lib "eagle-import") (part "C-EUC0603"))
    )
    (comp (ref "C19")
      (value "4.7uF")
      (footprint "eagle-import:C0603")
      (libsource (lib "eagle-import") (part "C-EUC0603"))
    )
    (comp (ref "C20")
      (value "470nF")
      (footprint "eagle-import:C0603")
      (libsource (lib "eagle-import") (part "C-EUC0603"))
    )
    (comp (ref "C21")
      (value "470nF")
      (footprint "eagle-import:C0603")
      (libsource (lib "eagle-import") (part "C-EUC0603"))
    )
    (comp (ref "C22")
      (value "4.7uF")
      (footprint "eagle-import:C0603")
      (libsource (lib "eagle-import") (part "C-EUC0603"))
    )
    (comp (ref "C23")
      (value "470nF")
      (footprint "eagle-import:C0603")
      (libsource (lib "eagle-import") (part "C-EUC0603"))
    )
    (comp (ref "C24")
      (value "470nF")
      (footprint "eagle-import:C0603")
      (libsource (lib "eagle-import") (part "C-EUC0603"))
    )
    (comp (ref "C25")
      (value "4.7uF")
      (footprint "eagle-import:C0603")
      (libsource (lib "eagle-import") (part "C-EUC0603"))
    )
    (comp (ref "C26")
      (value "470nF")
      (footprint "eagle-import:C0603")
      (libsource (lib "eagle-import") (part "C-EUC0603"))
    )
    (comp (ref "C27")
      (value "470nF")
      (footprint "eagle-import:C0603")
      (libsource (lib "eagle-import") (part "C-EUC0603"))
    )
    (comp (ref "C28")
      (value "470nF")
      (footprint "eagle-import:C0603")
      (libsource (lib "eagle-import") (part "C-EUC0603"))
    )
    (comp (ref "C29")
      (value "470nF")
      (footprint "eagle-import:C0603")
      (libsource (lib "eagle-import") (part "C-EUC0603"))
    )
    (comp (ref "C30")
      (value "470nF")
      (footprint "eagle-import:C0603")
      (libsource (lib "eagle-import") (part "C-EUC0603"))
    )
    (comp (ref "C36")
      (value "10nF")
      (footprint "eagle-import:C0603")
      (libsource (lib "eagle-import") (part "C-EUC0603"))
    )
    (comp (ref "C37")
      (value "2.2uF")
      (footprint "eagle-import:C0603")
      (libsource (lib "eagle-import") (part "C-EUC0603"))
    )
    (comp (ref "C40")
      (value "2.2uF")
      (footprint "eagle-import:C0603")
      (libsource (lib "eagle-import") (part "C-EUC0603"))
    )
    (comp (ref "C41")
      (value "470nF")
      (footprint "eagle-import:C0603")
      (libsource (lib "eagle-import") (part "C-EUC0603"))
    )
    (comp (ref "C42")
      (value "470nF")
      (footprint "eagle-import:C0603")
      (libsource (lib "eagle-import") (part "C-EUC0603"))
    )
    (comp (ref "C43")
      (value "470nF")
      (footprint "eagle-import:C0603")
      (libsource (lib "eagle-import") (part "C-EUC0603"))
    )
    (comp (ref "IC2")
      (value "TPS73033DBV-1135395")
      (footprint "eagle-import:SOT23-DBV")
      (libsource (lib "eagle-import") (part "TPS73033DBV"))
    )
    (comp (ref "IC3")
      (value "LD6806TD/12H-2095494")
      (footprint "eagle-import:SOT23-DBV")
      (libsource (lib "eagle-import") (part "LD6806TD/12H"))
    )
    (comp (ref "IC6")
      (value "TPS73033DBV-1135395")
      (footprint "eagle-import:SOT23-DBV")
      (libsource (lib "eagle-import") (part "TPS73033DBV"))
    )
    (comp (ref "L1")
      (value "100nH")
      (footprint "eagle-import:R0805")
      (libsource (lib "eagle-import") (part "R-US_R0805"))
    )
    (comp (ref "L2")
      (value "100nH")
      (footprint "eagle-import:R0805")
      (libsource (lib "eagle-import") (part "R-US_R0805"))
    )
    (comp (ref "L3")
      (value "100nH")
      (footprint "eagle-import:R0805")
      (libsource (lib "eagle-import") (part "R-US_R0805"))
    )
    (comp (ref "R7")
      (value "330k")
      (footprint "eagle-import:R0603")
      (libsource (lib "eagle-import") (part "R-EU_R0603"))
    )
    (comp (ref "TP3")
      (value "TPTP15R")
      (footprint "eagle-import:TP15R")
      (libsource (lib "eagle-import") (part "TPTP15R"))
    )
    (comp (ref "TP8")
      (value "TPTP15R")
      (footprint "eagle-import:TP15R")
      (libsource (lib "eagle-import") (part "TPTP15R"))
    )
    (comp (ref "TP9")
      (value "TPTP15R")
      (footprint "eagle-import:TP15R")
      (libsource (lib "eagle-import") (part "TPTP15R"))
    )
    (comp (ref "TP10")
      (value "TPTP15R")
      (footprint "eagle-import:TP15R")
      (libsource (lib "eagle-import") (part "TPTP15R"))
    )
  )
  (nets
    (net (code "1") (name "+3V3") (class "Default")
      (node (ref "C13") (pin "1") (pinfunction "1_1") (pintype "passive"))
      (node (ref "C14") (pin "1") (pinfunction "1_1") (pintype "passive"))
      (node (ref "C15") (pin "1") (pinfunction "1_1") (pintype "passive"))
      (node (ref "C16") (pin "1") (pinfunction "1_1") (pintype "passive"))
      (node (ref "C17") (pin "1") (pinfunction "1_1") (pintype "passive"))
      (node (ref "C21") (pin "1") (pinfunction "1_1") (pintype "passive"))
      (node (ref "C22") (pin "1") (pinfunction "1_1") (pintype "passive"))
      (node (ref "C23") (pin "1") (pinfunction "1_1") (pintype "passive"))
      (node (ref "C24") (pin "1") (pinfunction "1_1") (pintype "passive"))
      (node (ref "C25") (pin "1") (pinfunction "1_1") (pintype "passive"))
      (node (ref "C26") (pin "1") (pinfunction "1_1") (pintype "passive"))
      (node (ref "C27") (pin "1") (pinfunction "1_1") (pintype "passive"))
      (node (ref "C28") (pin "1") (pinfunction "1_1") (pintype "passive"))
      (node (ref "C29") (pin "1") (pinfunction "1_1") (pintype "passive"))
      (node (ref "C30") (pin "1") (pinfunction "1_1") (pintype "passive"))
      (node (ref "C31") (pin "1") (pinfunction "1_1") (pintype "passive"))
      (node (ref "C32") (pin "1") (pinfunction "1_1") (pintype "passive"))
      (node (ref "C33") (pin "1") (pinfunction "1_1") (pintype "passive"))
      (node (ref "C38") (pin "1") (pinfunction "1_1") (pintype "passive"))
      (node (ref "IC1") (pin "103") (pinfunction "VCCO_1_103") (pintype "power_in"))
      (node (ref "IC1") (pin "122") (pinfunction "VCC_0_122") (pintype "power_in"))
      (node (ref "IC1") (pin "125") (pinfunction "VCC_0_125") (pintype "power_in"))
      (node (ref "IC1") (pin "135") (pinfunction "VCC_0_135") (pintype "power_in"))
      (node (ref "IC1") (pin "144") (pinfunction "IO_L1P_HSWAPEN_0_144") (pintype "bidirectional"))
      (node (ref "IC1") (pin "18") (pinfunction "VCCO_3_18") (pintype "power_in"))
      (node (ref "IC1") (pin "31") (pinfunction "VCCO_3_31") (pintype "power_in"))
      (node (ref "IC1") (pin "4") (pinfunction "VCCO_3_4") (pintype "power_in"))
      (node (ref "IC1") (pin "42") (pinfunction "VCCO_2_42") (pintype "power_in"))
      (node (ref "IC1") (pin "63") (pinfunction "VCCO_2_63") (pintype "power_in"))
      (node (ref "IC1") (pin "69") (pinfunction "IO_L1N_M0_CMPMISO_2_69") (pintype "bidirectional"))
      (node (ref "IC1") (pin "76") (pinfunction "VCCO_1_76") (pintype "power_in"))
      (node (ref "IC1") (pin "86") (pinfunction "VCCO_1_86") (pintype "power_in"))
      (node (ref "IC5") (pin "3") (pinfunction "WP_(IO2)_3") (pintype "bidirectional"))
      (node (ref "IC5") (pin "7") (pinfunction "HOLD_(IO3)_7") (pintype "bidirectional"))
      (node (ref "IC5") (pin "8") (pinfunction "VCC_8") (pintype "power_in"))
      (node (ref "L3") (pin "2") (pinfunction "2_2") (pintype "passive"))
      (node (ref "Q4") (pin "2") (pinfunction "E_2") (pintype "passive"))
      (node (ref "R10") (pin "1") (pinfunction "1_1") (pintype "passive"))
      (node (ref "R5") (pin "2") (pinfunction "2_2") (pintype "passive"))
      (node (ref "R6") (pin "2") (pinfunction "2_2") (pintype "passive"))
      (node (ref "TR1") (pin "1") (pinfunction "VCCA_1") (pintype "passive"))
      (node (ref "TR10") (pin "1") (pinfunction "VCCA_1") (pintype "passive"))
      (node (ref "TR11") (pin "1") (pinfunction "VCCA_1") (pintype "passive"))
      (node (ref "TR12") (pin "1") (pinfunction "VCCA_1") (pintype "passive"))
      (node (ref "TR13") (pin "1") (pinfunction "VCCA_1") (pintype "passive"))
      (node (ref "TR14") (pin "1") (pinfunction "VCCA_1") (pintype "passive"))
      (node (ref "TR15") (pin "1") (pinfunction "VCCA_1") (pintype "passive"))
      (node (ref "TR16") (pin "1") (pinfunction "VCCA_1") (pintype "passive"))
      (node (ref "TR2") (pin "1") (pinfunction "VCCA_1") (pintype "passive"))
      (node (ref "TR3") (pin "1") (pinfunction "VCCA_1") (pintype "passive"))
      (node (ref "TR4") (pin "1") (pinfunction "VCCA_1") (pintype "passive"))
      (node (ref "TR5") (pin "1") (pinfunction "VCCA_1") (pintype "passive"))
      (node (ref "TR6") (pin "1") (pinfunction "VCCA_1") (pintype "passive"))
      (node (ref "TR7") (pin "1") (pinfunction "VCCA_1") (pintype "passive"))
      (node (ref "TR8") (pin "1") (pinfunction "VCCA_1") (pintype "passive"))
      (node (ref "TR9") (pin "1") (pinfunction "VCCA_1") (pintype "passive"))
      (node (ref "U$1") (pin "5") (pinfunction "VCC_5") (pintype "passive"))
      (node (ref "X2") (pin "1") (pinfunction "EN_1") (pintype "bidirectional"))
      (node (ref "X2") (pin "4") (pinfunction "VCC_4") (pintype "passive"))
    )
    (net (code "2") (name "+5V") (class "Default")
      (node (ref "C40") (pin "1") (pinfunction "1_1") (pintype "passive"))
      (node (ref "C6") (pin "1") (pinfunction "1_1") (pintype "passive"))
      (node (ref "IC2") (pin "1") (pinfunction "IN_1") (pintype "passive"))
      (node (ref "IC2") (pin "3") (pinfunction "EN_3") (pintype "input"))
      (node (ref "IC3") (pin "1") (pinfunction "IN_1") (pintype "passive"))
      (node (ref "IC3") (pin "3") (pinfunction "EN_3") (pintype "input"))
      (node (ref "IC6") (pin "1") (pinfunction "IN_1") (pintype "passive"))
      (node (ref "JP10") (pin "1") (pinfunction "1_1") (pintype "passive"))
      (node (ref "JP9") (pin "1") (pinfunction "1_1") (pintype "passive"))
      (node (ref "Q2") (pin "2") (pinfunction "E_2") (pintype "passive"))
      (node (ref "TP10") (pin "TP") (pinfunction "TP_TP") (pintype "input"))
      (node (ref "X1") (pin "1") (pinfunction "VBUS_1") (pintype "passive"))
    )
    (net (code "3") (name "AD_RA0") (class "Default")
      (node (ref "IC1") (pin "46") (pinfunction "IO_L49P_D3_2_46") (pintype "bidirectional"))
      (node (ref "U$1") (pin "1") (pinfunction "ICSPDAT/RA0_1") (pintype "bidirectional"))
    )
    (net (code "4") (name "AD_RA1") (class "Default")
      (node (ref "IC1") (pin "47") (pinfunction "IO_L48N_RDWR_B_VREF_2_47") (pintype "bidirectional"))
      (node (ref "U$1") (pin "3") (pinfunction "ICSPCLK/RA1_3") (pintype "bidirectional"))
    )
    (net (code "5") (name "AD_RA3") (class "Default")
      (node (ref "IC1") (pin "51") (pinfunction "IO_L31P_GCLK31_D14_2_51") (pintype "bidirectional"))
      (node (ref "U$1") (pin "6") (pinfunction "MCLRB/VPP/RA3_6") (pintype "input"))
    )
    (net (code "6") (name "CFG_DONE") (class "Default")
      (node (ref "IC1") (pin "71") (pinfunction "DONE_2_71") (pintype "bidirectional"))
      (node (ref "R59") (pin "1") (pinfunction "1_1") (pintype "passive"))
    )
    (net (code "7") (name "CLK_33") (class "Default")
      (node (ref "IC1") (pin "134") (pinfunction "IO_L34P_GCLK19_0_134") (pintype "bidirectional"))
      (node (ref "X2") (pin "3") (pinfunction "OUT_3") (pintype "output"))
    )
    (net (code "8") (name "FLASH_CLK") (class "Default")
      (node (ref "IC1") (pin "70") (pinfunction "IO_L1P_CCLK_2_70") (pintype "bidirectional"))
      (node (ref "IC5") (pin "6") (pinfunction "CLK_6") (pintype "input"))
    )
    (net (code "9") (name "FLASH_CS") (class "Default")
      (node (ref "IC1") (pin "38") (pinfunction "IO_L65N_CSO_B_2_38") (pintype "bidirectional"))
      (node (ref "IC5") (pin "1") (pinfunction "CS_1") (pintype "input"))
      (node (ref "R5") (pin "1") (pinfunction "1_1") (pintype "passive"))
    )
    (net (code "10") (name "FLASH_SI") (class "Default")
      (node (ref "IC1") (pin "64") (pinfunction "IO_L3N_MOSI_CSI_B_MISO0_2_64") (pintype "bidirectional"))
      (node (ref "IC5") (pin "5") (pinfunction "SI_(IO0)_5") (pintype "bidirectional"))
    )
    (net (code "11") (name "FLASH_SO") (class "Default")
      (node (ref "IC1") (pin "65") (pinfunction "IO_L3P_D0_DIN_MISO_MISO1_2_65") (pintype "bidirectional"))
      (node (ref "IC5") (pin "2") (pinfunction "SO_(IO1)_2") (pintype "output"))
    )
    (net (code "12") (name "GND") (class "Default")
      (node (ref "C1") (pin "2") (pinfunction "2_2") (pintype "passive"))
      (node (ref "C10") (pin "2") (pinfunction "2_2") (pintype "passive"))
      (node (ref "C11") (pin "2") (pinfunction "2_2") (pintype "passive"))
      (node (ref "C12") (pin "2") (pinfunction "2_2") (pintype "passive"))
      (node (ref "C13") (pin "2") (pinfunction "2_2") (pintype "passive"))
      (node (ref "C14") (pin "2") (pinfunction "2_2") (pintype "passive"))
      (node (ref "C15") (pin "2") (pinfunction "2_2") (pintype "passive"))
      (node (ref "C16") (pin "2") (pinfunction "2_2") (pintype "passive"))
      (node (ref "C17") (pin "2") (pinfunction "2_2") (pintype "passive"))
      (node (ref "C18") (pin "2") (pinfunction "2_2") (pintype "passive"))
      (node (ref "C19") (pin "2") (pinfunction "2_2") (pintype "passive"))
      (node (ref "C2") (pin "2") (pinfunction "2_2") (pintype "passive"))
      (node (ref "C20") (pin "2") (pinfunction "2_2") (pintype "passive"))
      (node (ref "C21") (pin "2") (pinfunction "2_2") (pintype "passive"))
      (node (ref "C22") (pin "2") (pinfunction "2_2") (pintype "passive"))
      (node (ref "C23") (pin "2") (pinfunction "2_2") (pintype "passive"))
      (node (ref "C24") (pin "2") (pinfunction "2_2") (pintype "passive"))
      (node (ref "C25") (pin "2") (pinfunction "2_2") (pintype "passive"))
      (node (ref "C26") (pin "2") (pinfunction "2_2") (pintype "passive"))
      (node (ref "C27") (pin "2") (pinfunction "2_2") (pintype "passive"))
      (node (ref "C28") (pin "2") (pinfunction "2_2") (pintype "passive"))
      (node (ref "C29") (pin "2") (pinfunction "2_2") (pintype "passive"))
      (node (ref "C3") (pin "2") (pinfunction "2_2") (pintype "passive"))
      (node (ref "C30") (pin "2") (pinfunction "2_2") (pintype "passive"))
      (node (ref "C31") (pin "2") (pinfunction "2_2") (pintype "passive"))
      (node (ref "C32") (pin "2") (pinfunction "2_2") (pintype "passive"))
      (node (ref "C33") (pin "2") (pinfunction "2_2") (pintype "passive"))
      (node (ref "C34") (pin "2") (pinfunction "2_2") (pintype "passive"))
      (node (ref "C35") (pin "2") (pinfunction "2_2") (pintype "passive"))
      (node (ref "C36") (pin "2") (pinfunction "2_2") (pintype "passive"))
      (node (ref "C37") (pin "2") (pinfunction "2_2") (pintype "passive"))
      (node (ref "C38") (pin "2") (pinfunction "2_2") (pintype "passive"))
      (node (ref "C39") (pin "2") (pinfunction "2_2") (pintype "passive"))
      (node (ref "C4") (pin "2") (pinfunction "2_2") (pintype "passive"))
      (node (ref "C40") (pin "2") (pinfunction "2_2") (pintype "passive"))
      (node (ref "C41") (pin "2") (pinfunction "2_2") (pintype "passive"))
      (node (ref "C42") (pin "2") (pinfunction "2_2") (pintype "passive"))
      (node (ref "C43") (pin "2") (pinfunction "2_2") (pintype "passive"))
      (node (ref "C5") (pin "2") (pinfunction "2_2") (pintype "passive"))
      (node (ref "C6") (pin "2") (pinfunction "2_2") (pintype "passive"))
      (node (ref "C7") (pin "2") (pinfunction "2_2") (pintype "passive"))
      (node (ref "C8") (pin "2") (pinfunction "2_2") (pintype "passive"))
      (node (ref "C9") (pin "2") (pinfunction "2_2") (pintype "passive"))
      (node (ref "IC1") (pin "108") (pinfunction "GND_108") (pintype "power_in"))
      (node (ref "IC1") (pin "113") (pinfunction "GND_113") (pintype "power_in"))
      (node (ref "IC1") (pin "13") (pinfunction "GND_13") (pintype "power_in"))
      (node (ref "IC1") (pin "130") (pinfunction "GND_130") (pintype "power_in"))
      (node (ref "IC1") (pin "136") (pinfunction "GND_136") (pintype "power_in"))
      (node (ref "IC1") (pin "25") (pinfunction "GND_25") (pintype "power_in"))
      (node (ref "IC1") (pin "3") (pinfunction "GND_3") (pintype "power_in"))
      (node (ref "IC1") (pin "49") (pinfunction "GND_49") (pintype "power_in"))
      (node (ref "IC1") (pin "54") (pinfunction "GND_54") (pintype "power_in"))
      (node (ref "IC1") (pin "60") (pinfunction "IO_L13P_M1_2_60") (pintype "bidirectional"))
      (node (ref "IC1") (pin "68") (pinfunction "GND_68") (pintype "power_in"))
      (node (ref "IC1") (pin "73") (pinfunction "SUSPEND_73") (pintype "input"))
      (node (ref "IC1") (pin "77") (pinfunction "GND_77") (pintype "power_in"))
      (node (ref "IC1") (pin "91") (pinfunction "GND_91") (pintype "power_in"))
      (node (ref "IC1") (pin "96") (pinfunction "GND_96") (pintype "power_in"))
      (node (ref "IC2") (pin "2") (pinfunction "GND_2") (pintype "passive"))
      (node (ref "IC3") (pin "2") (pinfunction "GND_2") (pintype "passive"))
      (node (ref "IC4") (pin "12") (pinfunction "VSSQ_12") (pintype "power_in"))
      (node (ref "IC4") (pin "28") (pinfunction "VSS_28") (pintype "power_in"))
      (node (ref "IC4") (pin "41") (pinfunction "VSS_41") (pintype "power_in"))
      (node (ref "IC4") (pin "46") (pinfunction "VSSQ_46") (pintype "power_in"))
      (node (ref "IC4") (pin "52") (pinfunction "VSSQ_52") (pintype "power_in"))
      (node (ref "IC4") (pin "54") (pinfunction "VSS_54") (pintype "power_in"))
      (node (ref "IC4") (pin "6") (pinfunction "VSSQ_6") (pintype "power_in"))
      (node (ref "IC5") (pin "4") (pinfunction "GND_4") (pintype "passive"))
      (node (ref "IC6") (pin "2") (pinfunction "GND_2") (pintype "passive"))
      (node (ref "JP5") (pin "1") (pinfunction "1_1") (pintype "passive"))
      (node (ref "JP6") (pin "1") (pinfunction "1_1") (pintype "passive"))
      (node (ref "JP7") (pin "1") (pinfunction "1_1") (pintype "passive"))
      (node (ref "JP8") (pin "1") (pinfunction "1_1") (pintype "passive"))
      (node (ref "LED1") (pin "C") (pinfunction "C_C") (pintype "passive"))
      (node (ref "LED2") (pin "C") (pinfunction "C_C") (pintype "passive"))
      (node (ref "LED3") (pin "C") (pinfunction "C_C") (pintype "passive"))
      (node (ref "LED4") (pin "C") (pinfunction "C_C") (pintype "passive"))
      (node (ref "LED5") (pin "C") (pinfunction "C_C") (pintype "passive"))
      (node (ref "Q1") (pin "2") (pinfunction "E_2") (pintype "passive"))
      (node (ref "Q3") (pin "2") (pinfunction "E_2") (pintype "passive"))
      (node (ref "R27") (pin "1") (pinfunction "1_1") (pintype "passive"))
      (node (ref "R28") (pin "1") (pinfunction "1_1") (pintype "passive"))
      (node (ref "R29") (pin "1") (pinfunction "1_1") (pintype "passive"))
      (node (ref "R30") (pin "1") (pinfunction "1_1") (pintype "passive"))
      (node (ref "R31") (pin "1") (pinfunction "1_1") (pintype "passive"))
      (node (ref "R32") (pin "1") (pinfunction "1_1") (pintype "passive"))
      (node (ref "R33") (pin "1") (pinfunction "1_1") (pintype "passive"))
      (node (ref "R34") (pin "1") (pinfunction "1_1") (pintype "passive"))
      (node (ref "R35") (pin "1") (pinfunction "1_1") (pintype "passive"))
      (node (ref "R36") (pin "1") (pinfunction "1_1") (pintype "passive"))
      (node (ref "R37") (pin "1") (pinfunction "1_1") (pintype "passive"))
      (node (ref "R38") (pin "1") (pinfunction "1_1") (pintype "passive"))
      (node (ref "R39") (pin "1") (pinfunction "1_1") (pintype "passive"))
      (node (ref "R40") (pin "1") (pinfunction "1_1") (pintype "passive"))
      (node (ref "R41") (pin "1") (pinfunction "1_1") (pintype "passive"))
      (node (ref "R42") (pin "1") (pinfunction "1_1") (pintype "passive"))
      (node (ref "R43") (pin "1") (pinfunction "1_1") (pintype "passive"))
      (node (ref "R44") (pin "1") (pinfunction "1_1") (pintype "passive"))
      (node (ref "R45") (pin "1") (pinfunction "1_1") (pintype "passive"))
      (node (ref "R46") (pin "1") (pinfunction "1_1") (pintype "passive"))
      (node (ref "R47") (pin "1") (pinfunction "1_1") (pintype "passive"))
      (node (ref "R48") (pin "1") (pinfunction "1_1") (pintype "passive"))
      (node (ref "R49") (pin "1") (pinfunction "1_1") (pintype "passive"))
      (node (ref "R50") (pin "1") (pinfunction "1_1") (pintype "passive"))
      (node (ref "R51") (pin "1") (pinfunction "1_1") (pintype "passive"))
      (node (ref "R52") (pin "1") (pinfunction "1_1") (pintype "passive"))
      (node (ref "R53") (pin "1") (pinfunction "1_1") (pintype "passive"))
      (node (ref "R54") (pin "1") (pinfunction "1_1") (pintype "passive"))
      (node (ref "R55") (pin "1") (pinfunction "1_1") (pintype "passive"))
      (node (ref "R56") (pin "1") (pinfunction "1_1") (pintype "passive"))
      (node (ref "R57") (pin "1") (pinfunction "1_1") (pintype "passive"))
      (node (ref "R58") (pin "1") (pinfunction "1_1") (pintype "passive"))
      (node (ref "R62") (pin "1") (pinfunction "1_1") (pintype "passive"))
      (node (ref "R7") (pin "1") (pinfunction "1_1") (pintype "passive"))
      (node (ref "TP2") (pin "TP") (pinfunction "TP_TP") (pintype "input"))
      (node (ref "TR1") (pin "2") (pinfunction "GND_2") (pintype "passive"))
      (node (ref "TR10") (pin "2") (pinfunction "GND_2") (pintype "passive"))
      (node (ref "TR11") (pin "2") (pinfunction "GND_2") (pintype "passive"))
      (node (ref "TR12") (pin "2") (pinfunction "GND_2") (pintype "passive"))
      (node (ref "TR13") (pin "2") (pinfunction "GND_2") (pintype "passive"))
      (node (ref "TR14") (pin "2") (pinfunction "GND_2") (pintype "passive"))
      (node (ref "TR15") (pin "2") (pinfunction "GND_2") (pintype "passive"))
      (node (ref "TR16") (pin "2") (pinfunction "GND_2") (pintype "passive"))
      (node (ref "TR2") (pin "2") (pinfunction "GND_2") (pintype "passive"))
      (node (ref "TR3") (pin "2") (pinfunction "GND_2") (pintype "passive"))
      (node (ref "TR4") (pin "2") (pinfunction "GND_2") (pintype "passive"))
      (node (ref "TR5") (pin "2") (pinfunction "GND_2") (pintype "passive"))
      (node (ref "TR6") (pin "2") (pinfunction "GND_2") (pintype "passive"))
      (node (ref "TR7") (pin "2") (pinfunction "GND_2") (pintype "passive"))
      (node (ref "TR8") (pin "2") (pinfunction "GND_2") (pintype "passive"))
      (node (ref "TR9") (pin "2") (pinfunction "GND_2") (pintype "passive"))
      (node (ref "U$1") (pin "2") (pinfunction "GND_2") (pintype "passive"))
      (node (ref "X1") (pin "5") (pinfunction "GND_5") (pintype "passive"))
      (node (ref "X2") (pin "2") (pinfunction "GND_2") (pintype "passive"))
    )
    (net (code "13") (name "LED1") (class "Default")
      (node (ref "IC1") (pin "139") (pinfunction "IO_L3N_0_139") (pintype "bidirectional"))
      (node (ref "R4") (pin "1") (pinfunction "1_1") (pintype "passive"))
    )
    (net (code "14") (name "LED2") (class "Default")
      (node (ref "IC1") (pin "138") (pinfunction "IO_L4P_0_138") (pintype "bidirectional"))
      (node (ref "R8") (pin "1") (pinfunction "1_1") (pintype "passive"))
    )
    (net (code "15") (name "LED3") (class "Default")
      (node (ref "IC1") (pin "133") (pinfunction "IO_L34N_GCLK18_0_133") (pintype "bidirectional"))
      (node (ref "R9") (pin "1") (pinfunction "1_1") (pintype "passive"))
    )
    (net (code "16") (name "M_A0") (class "Default")
      (node (ref "IC1") (pin "79") (pinfunction "IO_L47P_1_79") (pintype "bidirectional"))
      (node (ref "IC4") (pin "23") (pinfunction "A0_23") (pintype "input"))
    )
    (net (code "17") (name "M_A1") (class "Default")
      (node (ref "IC1") (pin "78") (pinfunction "IO_L47N_1_78") (pintype "bidirectional"))
      (node (ref "IC4") (pin "24") (pinfunction "A1_24") (pintype "input"))
    )
    (net (code "18") (name "M_A2") (class "Default")
      (node (ref "IC1") (pin "75") (pinfunction "IO_L74P_AWAKE_1_75") (pintype "bidirectional"))
      (node (ref "IC4") (pin "25") (pinfunction "A2_25") (pintype "input"))
    )
    (net (code "19") (name "M_A3") (class "Default")
      (node (ref "IC1") (pin "74") (pinfunction "IO_L74N_DOUT_BUSY_1_74") (pintype "bidirectional"))
      (node (ref "IC4") (pin "26") (pinfunction "A3_26") (pintype "input"))
    )
    (net (code "20") (name "M_A4") (class "Default")
      (node (ref "IC1") (pin "132") (pinfunction "IO_L35P_GCLK17_0_132") (pintype "bidirectional"))
      (node (ref "IC4") (pin "29") (pinfunction "A4_29") (pintype "input"))
    )
    (net (code "21") (name "M_A5") (class "Default")
      (node (ref "IC1") (pin "102") (pinfunction "IO_L32P_1_102") (pintype "bidirectional"))
      (node (ref "IC4") (pin "30") (pinfunction "A5_30") (pintype "input"))
    )
    (net (code "22") (name "M_A6") (class "Default")
      (node (ref "IC1") (pin "104") (pinfunction "IO_L1N_VREF_1_104") (pintype "bidirectional"))
      (node (ref "IC4") (pin "31") (pinfunction "A6_31") (pintype "input"))
    )
    (net (code "23") (name "M_A7") (class "Default")
      (node (ref "IC1") (pin "131") (pinfunction "IO_L35N_GCLK16_0_131") (pintype "bidirectional"))
      (node (ref "IC4") (pin "32") (pinfunction "A7_32") (pintype "input"))
    )
    (net (code "24") (name "M_A8") (class "Default")
      (node (ref "IC1") (pin "127") (pinfunction "IO_L36P_GCLK15_0_127") (pintype "bidirectional"))
      (node (ref "IC4") (pin "33") (pinfunction "A8_33") (pintype "input"))
    )
    (net (code "25") (name "M_A9") (class "Default")
      (node (ref "IC1") (pin "126") (pinfunction "IO_L36N_GCLK14_0_126") (pintype "bidirectional"))
      (node (ref "IC4") (pin "34") (pinfunction "A9_34") (pintype "input"))
    )
    (net (code "26") (name "M_A10") (class "Default")
      (node (ref "IC1") (pin "80") (pinfunction "IO_L46N_1_80") (pintype "bidirectional"))
      (node (ref "IC4") (pin "22") (pinfunction "A10_22") (pintype "input"))
    )
    (net (code "27") (name "M_A11") (class "Default")
      (node (ref "IC1") (pin "124") (pinfunction "IO_L37P_GCLK13_0_124") (pintype "bidirectional"))
      (node (ref "IC4") (pin "35") (pinfunction "A11_35") (pintype "input"))
    )
    (net (code "28") (name "M_A12") (class "Default")
      (node (ref "IC1") (pin "123") (pinfunction "IO_L37N_GCLK12_0_123") (pintype "bidirectional"))
      (node (ref "IC4") (pin "36") (pinfunction "A12_36") (pintype "input"))
    )
    (net (code "29") (name "M_BA0") (class "Default")
      (node (ref "IC1") (pin "82") (pinfunction "IO_L45N_1_82") (pintype "bidirectional"))
      (node (ref "IC4") (pin "20") (pinfunction "BA0_20") (pintype "input"))
    )
    (net (code "30") (name "M_BA1") (class "Default")
      (node (ref "IC1") (pin "81") (pinfunction "IO_L46P_1_81") (pintype "bidirectional"))
      (node (ref "IC4") (pin "21") (pinfunction "BA1_21") (pintype "input"))
    )
    (net (code "31") (name "M_CAS") (class "Default")
      (node (ref "IC1") (pin "85") (pinfunction "IO_L43P_GCLK5_1_85") (pintype "bidirectional"))
      (node (ref "IC4") (pin "17") (pinfunction "~{CAS}_17") (pintype "input"))
    )
    (net (code "32") (name "M_CKE") (class "Default")
      (node (ref "IC1") (pin "121") (pinfunction "IO_L62P_0_121") (pintype "bidirectional"))
      (node (ref "IC4") (pin "37") (pinfunction "CKE_37") (pintype "input"))
    )
    (net (code "33") (name "M_CLK") (class "Default")
      (node (ref "IC1") (pin "105") (pinfunction "IO_L1P_1_105") (pintype "bidirectional"))
      (node (ref "IC4") (pin "38") (pinfunction "CLK_38") (pintype "input"))
    )
    (net (code "34") (name "M_CS") (class "Default")
      (node (ref "IC1") (pin "83") (pinfunction "IO_L45P_1_83") (pintype "bidirectional"))
      (node (ref "IC4") (pin "19") (pinfunction "\\CS_19") (pintype "input"))
    )
    (net (code "35") (name "M_DQ0") (class "Default")
      (node (ref "IC1") (pin "92") (pinfunction "IO_L41N_GCLK8_1_92") (pintype "bidirectional"))
      (node (ref "IC4") (pin "2") (pinfunction "DQ0_2") (pintype "tri_state"))
    )
    (net (code "36") (name "M_DQ1") (class "Default")
      (node (ref "IC1") (pin "93") (pinfunction "IO_L41P_GCLK9_IRDY1_1_93") (pintype "bidirectional"))
      (node (ref "IC4") (pin "4") (pinfunction "DQ1_4") (pintype "tri_state"))
    )
    (net (code "37") (name "M_DQ2") (class "Default")
      (node (ref "IC1") (pin "94") (pinfunction "IO_L40N_GCLK10_1_94") (pintype "bidirectional"))
      (node (ref "IC4") (pin "5") (pinfunction "DQ2_5") (pintype "tri_state"))
    )
    (net (code "38") (name "M_DQ3") (class "Default")
      (node (ref "IC1") (pin "95") (pinfunction "IO_L40P_GCLK11_1_95") (pintype "bidirectional"))
      (node (ref "IC4") (pin "7") (pinfunction "DQ3_7") (pintype "tri_state"))
    )
    (net (code "39") (name "M_DQ4") (class "Default")
      (node (ref "IC1") (pin "97") (pinfunction "IO_L34N_1_97") (pintype "bidirectional"))
      (node (ref "IC4") (pin "8") (pinfunction "DQ4_8") (pintype "tri_state"))
    )
    (net (code "40") (name "M_DQ5") (class "Default")
      (node (ref "IC1") (pin "98") (pinfunction "IO_L34P_1_98") (pintype "bidirectional"))
      (node (ref "IC4") (pin "10") (pinfunction "DQ5_10") (pintype "tri_state"))
    )
    (net (code "41") (name "M_DQ6") (class "Default")
      (node (ref "IC1") (pin "99") (pinfunction "IO_L33N_1_99") (pintype "bidirectional"))
      (node (ref "IC4") (pin "11") (pinfunction "DQ6_11") (pintype "tri_state"))
    )
    (net (code "42") (name "M_DQ7") (class "Default")
      (node (ref "IC1") (pin "100") (pinfunction "IO_L33P_1_100") (pintype "bidirectional"))
      (node (ref "IC4") (pin "13") (pinfunction "DQ7_13") (pintype "tri_state"))
    )
    (net (code "43") (name "M_DQ8") (class "Default")
      (node (ref "IC1") (pin "119") (pinfunction "IO_L63P_SCP7_0_119") (pintype "bidirectional"))
      (node (ref "IC4") (pin "42") (pinfunction "DQ8_42") (pintype "tri_state"))
    )
    (net (code "44") (name "M_DQ9") (class "Default")
      (node (ref "IC1") (pin "118") (pinfunction "IO_L63N_SCP6_0_118") (pintype "bidirectional"))
      (node (ref "IC4") (pin "44") (pinfunction "DQ9_44") (pintype "tri_state"))
    )
    (net (code "45") (name "M_DQ10") (class "Default")
      (node (ref "IC1") (pin "117") (pinfunction "IO_L64P_SCP5_0_117") (pintype "bidirectional"))
      (node (ref "IC4") (pin "45") (pinfunction "DQ10_45") (pintype "tri_state"))
    )
    (net (code "46") (name "M_DQ11") (class "Default")
      (node (ref "IC1") (pin "116") (pinfunction "IO_L64N_SCP4_0_116") (pintype "bidirectional"))
      (node (ref "IC4") (pin "47") (pinfunction "DQ11_47") (pintype "tri_state"))
    )
    (net (code "47") (name "M_DQ12") (class "Default")
      (node (ref "IC1") (pin "115") (pinfunction "IO_L65P_SCP3_0_115") (pintype "bidirectional"))
      (node (ref "IC4") (pin "48") (pinfunction "DQ12_48") (pintype "tri_state"))
    )
    (net (code "48") (name "M_DQ13") (class "Default")
      (node (ref "IC1") (pin "114") (pinfunction "IO_L65N_SCP2_0_114") (pintype "bidirectional"))
      (node (ref "IC4") (pin "50") (pinfunction "DQ13_50") (pintype "tri_state"))
    )
    (net (code "49") (name "M_DQ14") (class "Default")
      (node (ref "IC1") (pin "112") (pinfunction "IO_L66P_SCP1_0_112") (pintype "bidirectional"))
      (node (ref "IC4") (pin "51") (pinfunction "DQ14_51") (pintype "tri_state"))
    )
    (net (code "50") (name "M_DQ15") (class "Default")
      (node (ref "IC1") (pin "111") (pinfunction "IO_L66N_SCP0_0_111") (pintype "bidirectional"))
      (node (ref "IC4") (pin "53") (pinfunction "DQ15_53") (pintype "tri_state"))
    )
    (net (code "51") (name "M_DQMH") (class "Default")
      (node (ref "IC1") (pin "120") (pinfunction "IO_L62N_VREF_0_120") (pintype "bidirectional"))
      (node (ref "IC4") (pin "39") (pinfunction "DQMH_39") (pintype "input"))
    )
    (net (code "52") (name "M_DQML") (class "Default")
      (node (ref "IC1") (pin "88") (pinfunction "IO_L42P_GCLK7_1_88") (pintype "bidirectional"))
      (node (ref "IC4") (pin "15") (pinfunction "DQML_15") (pintype "input"))
    )
    (net (code "53") (name "M_PWREN") (class "Default")
      (node (ref "IC1") (pin "101") (pinfunction "IO_L32N_1_101") (pintype "bidirectional"))
      (node (ref "IC6") (pin "3") (pinfunction "EN_3") (pintype "input"))
      (node (ref "R7") (pin "2") (pinfunction "2_2") (pintype "passive"))
    )
    (net (code "54") (name "M_RAS") (class "Default")
      (node (ref "IC1") (pin "84") (pinfunction "IO_L43N_GCLK4_1_84") (pintype "bidirectional"))
      (node (ref "IC4") (pin "18") (pinfunction "~{RAS}_18") (pintype "input"))
    )
    (net (code "55") (name "M_WE") (class "Default")
      (node (ref "IC1") (pin "87") (pinfunction "IO_L42N_GCLK6_TRDY1_1_87") (pintype "bidirectional"))
      (node (ref "IC4") (pin "16") (pinfunction "~{WE}_16") (pintype "input"))
    )
    (net (code "56") (name "Net-(IC2-NR)") (class "Default")
      (node (ref "C1") (pin "1") (pinfunction "1_1") (pintype "passive"))
      (node (ref "IC2") (pin "4") (pinfunction "NR_4") (pintype "passive"))
    )
    (net (code "57") (name "Net-(IC2-OUT)") (class "Default")
      (node (ref "C2") (pin "1") (pinfunction "1_1") (pintype "passive"))
      (node (ref "IC2") (pin "5") (pinfunction "OUT_5") (pintype "passive"))
      (node (ref "L2") (pin "1") (pinfunction "1_1") (pintype "passive"))
      (node (ref "L3") (pin "1") (pinfunction "1_1") (pintype "passive"))
      (node (ref "TP9") (pin "TP") (pinfunction "TP_TP") (pintype "input"))
    )
    (net (code "58") (name "Net-(IC3-OUT)") (class "Default")
      (node (ref "C5") (pin "1") (pinfunction "1_1") (pintype "passive"))
      (node (ref "IC3") (pin "5") (pinfunction "OUT_5") (pintype "passive"))
      (node (ref "L1") (pin "1") (pinfunction "1_1") (pintype "passive"))
      (node (ref "TP8") (pin "TP") (pinfunction "TP_TP") (pintype "input"))
    )
    (net (code "59") (name "Net-(IC6-NR)") (class "Default")
      (node (ref "C36") (pin "1") (pinfunction "1_1") (pintype "passive"))
      (node (ref "IC6") (pin "4") (pinfunction "NR_4") (pintype "passive"))
    )
    (net (code "60") (name "Net-(IC6-OUT)") (class "Default")
      (node (ref "C37") (pin "1") (pinfunction "1_1") (pintype "passive"))
      (node (ref "C41") (pin "1") (pinfunction "1_1") (pintype "passive"))
      (node (ref "C42") (pin "1") (pinfunction "1_1") (pintype "passive"))
      (node (ref "C43") (pin "1") (pinfunction "1_1") (pintype "passive"))
      (node (ref "IC4") (pin "1") (pinfunction "VDD_1") (pintype "power_in"))
      (node (ref "IC4") (pin "14") (pinfunction "VDD_14") (pintype "power_in"))
      (node (ref "IC4") (pin "27") (pinfunction "VDD_27") (pintype "power_in"))
      (node (ref "IC4") (pin "3") (pinfunction "VDDQ_3") (pintype "power_in"))
      (node (ref "IC4") (pin "43") (pinfunction "VDDQ_43") (pintype "power_in"))
      (node (ref "IC4") (pin "49") (pinfunction "VDDQ_49") (pintype "power_in"))
      (node (ref "IC4") (pin "9") (pinfunction "VDDQ_9") (pintype "power_in"))
      (node (ref "IC6") (pin "5") (pinfunction "OUT_5") (pintype "passive"))
      (node (ref "TP3") (pin "TP") (pinfunction "TP_TP") (pintype "input"))
    )
    (net (code "61") (name "Net-(JP97-Pad1)") (class "Default")
      (node (ref "JP97") (pin "1") (pinfunction "1_1") (pintype "passive"))
      (node (ref "JP98") (pin "1") (pinfunction "1_1") (pintype "passive"))
      (node (ref "R19") (pin "2") (pinfunction "2_2") (pintype "passive"))
      (node (ref "R35") (pin "2") (pinfunction "2_2") (pintype "passive"))
    )
    (net (code "62") (name "Net-(JP100-Pad1)") (class "Default")
      (node (ref "JP100") (pin "1") (pinfunction "1_1") (pintype "passive"))
      (node (ref "JP99") (pin "1") (pinfunction "1_1") (pintype "passive"))
      (node (ref "R20") (pin "2") (pinfunction "2_2") (pintype "passive"))
      (node (ref "R36") (pin "2") (pinfunction "2_2") (pintype "passive"))
    )
    (net (code "63") (name "Net-(JP101-Pad1)") (class "Default")
      (node (ref "JP101") (pin "1") (pinfunction "1_1") (pintype "passive"))
      (node (ref "JP102") (pin "1") (pinfunction "1_1") (pintype "passive"))
      (node (ref "R21") (pin "2") (pinfunction "2_2") (pintype "passive"))
      (node (ref "R37") (pin "2") (pinfunction "2_2") (pintype "passive"))
    )
    (net (code "64") (name "Net-(JP103-Pad1)") (class "Default")
      (node (ref "JP103") (pin "1") (pinfunction "1_1") (pintype "passive"))
      (node (ref "JP104") (pin "1") (pinfunction "1_1") (pintype "passive"))
      (node (ref "R22") (pin "2") (pinfunction "2_2") (pintype "passive"))
      (node (ref "R38") (pin "2") (pinfunction "2_2") (pintype "passive"))
    )
    (net (code "65") (name "Net-(JP105-Pad1)") (class "Default")
      (node (ref "JP105") (pin "1") (pinfunction "1_1") (pintype "passive"))
      (node (ref "JP106") (pin "1") (pinfunction "1_1") (pintype "passive"))
      (node (ref "R23") (pin "2") (pinfunction "2_2") (pintype "passive"))
      (node (ref "R39") (pin "2") (pinfunction "2_2") (pintype "passive"))
    )
    (net (code "66") (name "Net-(JP107-Pad1)") (class "Default")
      (node (ref "JP107") (pin "1") (pinfunction "1_1") (pintype "passive"))
      (node (ref "JP108") (pin "1") (pinfunction "1_1") (pintype "passive"))
      (node (ref "R24") (pin "2") (pinfunction "2_2") (pintype "passive"))
      (node (ref "R40") (pin "2") (pinfunction "2_2") (pintype "passive"))
    )
    (net (code "67") (name "Net-(JP109-Pad1)") (class "Default")
      (node (ref "JP109") (pin "1") (pinfunction "1_1") (pintype "passive"))
      (node (ref "JP110") (pin "1") (pinfunction "1_1") (pintype "passive"))
      (node (ref "R25") (pin "2") (pinfunction "2_2") (pintype "passive"))
      (node (ref "R41") (pin "2") (pinfunction "2_2") (pintype "passive"))
    )
    (net (code "68") (name "Net-(JP111-Pad1)") (class "Default")
      (node (ref "JP111") (pin "1") (pinfunction "1_1") (pintype "passive"))
      (node (ref "JP112") (pin "1") (pinfunction "1_1") (pintype "passive"))
      (node (ref "R26") (pin "2") (pinfunction "2_2") (pintype "passive"))
      (node (ref "R42") (pin "2") (pinfunction "2_2") (pintype "passive"))
    )
    (net (code "69") (name "Net-(JP113-Pad1)") (class "Default")
      (node (ref "JP113") (pin "1") (pinfunction "1_1") (pintype "passive"))
      (node (ref "JP114") (pin "1") (pinfunction "1_1") (pintype "passive"))
      (node (ref "R11") (pin "2") (pinfunction "2_2") (pintype "passive"))
      (node (ref "R27") (pin "2") (pinfunction "2_2") (pintype "passive"))
    )
    (net (code "70") (name "Net-(JP115-Pad1)") (class "Default")
      (node (ref "JP115") (pin "1") (pinfunction "1_1") (pintype "passive"))
      (node (ref "JP116") (pin "1") (pinfunction "1_1") (pintype "passive"))
      (node (ref "R12") (pin "2") (pinfunction "2_2") (pintype "passive"))
      (node (ref "R28") (pin "2") (pinfunction "2_2") (pintype "passive"))
    )
    (net (code "71") (name "Net-(JP117-Pad1)") (class "Default")
      (node (ref "JP117") (pin "1") (pinfunction "1_1") (pintype "passive"))
      (node (ref "JP118") (pin "1") (pinfunction "1_1") (pintype "passive"))
      (node (ref "R13") (pin "2") (pinfunction "2_2") (pintype "passive"))
      (node (ref "R29") (pin "2") (pinfunction "2_2") (pintype "passive"))
    )
    (net (code "72") (name "Net-(JP119-Pad1)") (class "Default")
      (node (ref "JP119") (pin "1") (pinfunction "1_1") (pintype "passive"))
      (node (ref "JP120") (pin "1") (pinfunction "1_1") (pintype "passive"))
      (node (ref "R14") (pin "2") (pinfunction "2_2") (pintype "passive"))
      (node (ref "R30") (pin "2") (pinfunction "2_2") (pintype "passive"))
    )
    (net (code "73") (name "Net-(JP121-Pad1)") (class "Default")
      (node (ref "JP121") (pin "1") (pinfunction "1_1") (pintype "passive"))
      (node (ref "JP122") (pin "1") (pinfunction "1_1") (pintype "passive"))
      (node (ref "R15") (pin "2") (pinfunction "2_2") (pintype "passive"))
      (node (ref "R31") (pin "2") (pinfunction "2_2") (pintype "passive"))
    )
    (net (code "74") (name "Net-(JP123-Pad1)") (class "Default")
      (node (ref "JP123") (pin "1") (pinfunction "1_1") (pintype "passive"))
      (node (ref "JP124") (pin "1") (pinfunction "1_1") (pintype "passive"))
      (node (ref "R16") (pin "2") (pinfunction "2_2") (pintype "passive"))
      (node (ref "R32") (pin "2") (pinfunction "2_2") (pintype "passive"))
    )
    (net (code "75") (name "Net-(JP125-Pad1)") (class "Default")
      (node (ref "JP125") (pin "1") (pinfunction "1_1") (pintype "passive"))
      (node (ref "JP126") (pin "1") (pinfunction "1_1") (pintype "passive"))
      (node (ref "R17") (pin "2") (pinfunction "2_2") (pintype "passive"))
      (node (ref "R33") (pin "2") (pinfunction "2_2") (pintype "passive"))
    )
    (net (code "76") (name "Net-(JP127-Pad1)") (class "Default")
      (node (ref "JP127") (pin "1") (pinfunction "1_1") (pintype "passive"))
      (node (ref "JP128") (pin "1") (pinfunction "1_1") (pintype "passive"))
      (node (ref "R18") (pin "2") (pinfunction "2_2") (pintype "passive"))
      (node (ref "R34") (pin "2") (pinfunction "2_2") (pintype "passive"))
    )
    (net (code "77") (name "Net-(LED1-PadA)") (class "Default")
      (node (ref "LED1") (pin "A") (pinfunction "A_A") (pintype "passive"))
      (node (ref "R4") (pin "2") (pinfunction "2_2") (pintype "passive"))
    )
    (net (code "78") (name "Net-(LED2-PadA)") (class "Default")
      (node (ref "LED2") (pin "A") (pinfunction "A_A") (pintype "passive"))
      (node (ref "R8") (pin "2") (pinfunction "2_2") (pintype "passive"))
    )
    (net (code "79") (name "Net-(LED3-PadA)") (class "Default")
      (node (ref "LED3") (pin "A") (pinfunction "A_A") (pintype "passive"))
      (node (ref "R9") (pin "2") (pinfunction "2_2") (pintype "passive"))
    )
    (net (code "80") (name "Net-(LED4-PadA)") (class "Default")
      (node (ref "LED4") (pin "A") (pinfunction "A_A") (pintype "passive"))
      (node (ref "R10") (pin "2") (pinfunction "2_2") (pintype "passive"))
    )
    (net (code "81") (name "Net-(LED5-PadA)") (class "Default")
      (node (ref "LED5") (pin "A") (pinfunction "A_A") (pintype "passive"))
      (node (ref "R59") (pin "2") (pinfunction "2_2") (pintype "passive"))
    )
    (net (code "82") (name "Net-(Q1-C)") (class "Default")
      (node (ref "Q1") (pin "3") (pinfunction "C_3") (pintype "passive"))
      (node (ref "R60") (pin "2") (pinfunction "2_2") (pintype "passive"))
    )
    (net (code "83") (name "Net-(Q2-B)") (class "Default")
      (node (ref "Q2") (pin "1") (pinfunction "B_1") (pintype "passive"))
      (node (ref "R60") (pin "1") (pinfunction "1_1") (pintype "passive"))
    )
    (net (code "84") (name "Net-(Q3-C)") (class "Default")
      (node (ref "Q3") (pin "3") (pinfunction "C_3") (pintype "passive"))
      (node (ref "R61") (pin "2") (pinfunction "2_2") (pintype "passive"))
    )
    (net (code "85") (name "Net-(Q4-B)") (class "Default")
      (node (ref "Q4") (pin "1") (pinfunction "B_1") (pintype "passive"))
      (node (ref "R61") (pin "1") (pinfunction "1_1") (pintype "passive"))
    )
    (net (code "86") (name "Net-(TR1-B)") (class "Default")
      (node (ref "R11") (pin "1") (pinfunction "1_1") (pintype "passive"))
      (node (ref "TR1") (pin "4") (pinfunction "B_4") (pintype "bidirectional"))
    )
    (net (code "87") (name "Net-(TR2-B)") (class "Default")
      (node (ref "R12") (pin "1") (pinfunction "1_1") (pintype "passive"))
      (node (ref "TR2") (pin "4") (pinfunction "B_4") (pintype "bidirectional"))
    )
    (net (code "88") (name "Net-(TR3-B)") (class "Default")
      (node (ref "R13") (pin "1") (pinfunction "1_1") (pintype "passive"))
      (node (ref "TR3") (pin "4") (pinfunction "B_4") (pintype "bidirectional"))
    )
    (net (code "89") (name "Net-(TR4-B)") (class "Default")
      (node (ref "R14") (pin "1") (pinfunction "1_1") (pintype "passive"))
      (node (ref "TR4") (pin "4") (pinfunction "B_4") (pintype "bidirectional"))
    )
    (net (code "90") (name "Net-(TR5-B)") (class "Default")
      (node (ref "R15") (pin "1") (pinfunction "1_1") (pintype "passive"))
      (node (ref "TR5") (pin "4") (pinfunction "B_4") (pintype "bidirectional"))
    )
    (net (code "91") (name "Net-(TR6-B)") (class "Default")
      (node (ref "R16") (pin "1") (pinfunction "1_1") (pintype "passive"))
      (node (ref "TR6") (pin "4") (pinfunction "B_4") (pintype "bidirectional"))
    )
    (net (code "92") (name "Net-(TR7-B)") (class "Default")
      (node (ref "R17") (pin "1") (pinfunction "1_1") (pintype "passive"))
      (node (ref "TR7") (pin "4") (pinfunction "B_4") (pintype "bidirectional"))
    )
    (net (code "93") (name "Net-(TR8-B)") (class "Default")
      (node (ref "R18") (pin "1") (pinfunction "1_1") (pintype "passive"))
      (node (ref "TR8") (pin "4") (pinfunction "B_4") (pintype "bidirectional"))
    )
    (net (code "94") (name "Net-(TR9-B)") (class "Default")
      (node (ref "R19") (pin "1") (pinfunction "1_1") (pintype "passive"))
      (node (ref "TR9") (pin "4") (pinfunction "B_4") (pintype "bidirectional"))
    )
    (net (code "95") (name "Net-(TR10-B)") (class "Default")
      (node (ref "R20") (pin "1") (pinfunction "1_1") (pintype "passive"))
      (node (ref "TR10") (pin "4") (pinfunction "B_4") (pintype "bidirectional"))
    )
    (net (code "96") (name "Net-(TR11-B)") (class "Default")
      (node (ref "R21") (pin "1") (pinfunction "1_1") (pintype "passive"))
      (node (ref "TR11") (pin "4") (pinfunction "B_4") (pintype "bidirectional"))
    )
    (net (code "97") (name "Net-(TR12-B)") (class "Default")
      (node (ref "R22") (pin "1") (pinfunction "1_1") (pintype "passive"))
      (node (ref "TR12") (pin "4") (pinfunction "B_4") (pintype "bidirectional"))
    )
    (net (code "98") (name "Net-(TR13-B)") (class "Default")
      (node (ref "R23") (pin "1") (pinfunction "1_1") (pintype "passive"))
      (node (ref "TR13") (pin "4") (pinfunction "B_4") (pintype "bidirectional"))
    )
    (net (code "99") (name "Net-(TR14-B)") (class "Default")
      (node (ref "R24") (pin "1") (pinfunction "1_1") (pintype "passive"))
      (node (ref "TR14") (pin "4") (pinfunction "B_4") (pintype "bidirectional"))
    )
    (net (code "100") (name "Net-(TR15-B)") (class "Default")
      (node (ref "R25") (pin "1") (pinfunction "1_1") (pintype "passive"))
      (node (ref "TR15") (pin "4") (pinfunction "B_4") (pintype "bidirectional"))
    )
    (net (code "101") (name "Net-(TR16-B)") (class "Default")
      (node (ref "R26") (pin "1") (pinfunction "1_1") (pintype "passive"))
      (node (ref "TR16") (pin "4") (pinfunction "B_4") (pintype "bidirectional"))
    )
    (net (code "102") (name "Net-(U$1-RA2)") (class "Default")
      (node (ref "C39") (pin "1") (pinfunction "1_1") (pintype "passive"))
      (node (ref "R62") (pin "2") (pinfunction "2_2") (pintype "passive"))
      (node (ref "R63") (pin "2") (pinfunction "2_2") (pintype "passive"))
      (node (ref "U$1") (pin "4") (pinfunction "RA2_4") (pintype "bidirectional"))
    )
    (net (code "103") (name "RESET_N") (class "Default")
      (node (ref "IC1") (pin "37") (pinfunction "PROGRAM_B_2_37") (pintype "bidirectional"))
      (node (ref "R6") (pin "1") (pinfunction "1_1") (pintype "passive"))
      (node (ref "TP1") (pin "TP") (pinfunction "TP_TP") (pintype "input"))
    )
    (net (code "104") (name "S1") (class "Default")
      (node (ref "IC1") (pin "140") (pinfunction "IO_L3P_0_140") (pintype "bidirectional"))
      (node (ref "TR1") (pin "3") (pinfunction "A_3") (pintype "bidirectional"))
    )
    (net (code "105") (name "S2") (class "Default")
      (node (ref "IC1") (pin "142") (pinfunction "IO_L2P_0_142") (pintype "bidirectional"))
      (node (ref "TR2") (pin "3") (pinfunction "A_3") (pintype "bidirectional"))
    )
    (net (code "106") (name "S3") (class "Default")
      (node (ref "IC1") (pin "2") (pinfunction "IO_L83P_3_2") (pintype "bidirectional"))
      (node (ref "TR3") (pin "3") (pinfunction "A_3") (pintype "bidirectional"))
    )
    (net (code "107") (name "S4") (class "Default")
      (node (ref "IC1") (pin "6") (pinfunction "IO_L52P_3_6") (pintype "bidirectional"))
      (node (ref "TR4") (pin "3") (pinfunction "A_3") (pintype "bidirectional"))
    )
    (net (code "108") (name "S5") (class "Default")
      (node (ref "IC1") (pin "8") (pinfunction "IO_L51P_3_8") (pintype "bidirectional"))
      (node (ref "TR5") (pin "3") (pinfunction "A_3") (pintype "bidirectional"))
    )
    (net (code "109") (name "S6") (class "Default")
      (node (ref "IC1") (pin "10") (pinfunction "IO_L50P_3_10") (pintype "bidirectional"))
      (node (ref "TR6") (pin "3") (pinfunction "A_3") (pintype "bidirectional"))
    )
    (net (code "110") (name "S7") (class "Default")
      (node (ref "IC1") (pin "12") (pinfunction "IO_L49P_3_12") (pintype "bidirectional"))
      (node (ref "TR7") (pin "3") (pinfunction "A_3") (pintype "bidirectional"))
    )
    (net (code "111") (name "S8") (class "Default")
      (node (ref "IC1") (pin "15") (pinfunction "IO_L44P_GCLK21_3_15") (pintype "bidirectional"))
      (node (ref "TR8") (pin "3") (pinfunction "A_3") (pintype "bidirectional"))
    )
    (net (code "112") (name "S9") (class "Default")
      (node (ref "IC1") (pin "21") (pinfunction "IO_L42N_GCLK24_3_21") (pintype "bidirectional"))
      (node (ref "TR9") (pin "3") (pinfunction "A_3") (pintype "bidirectional"))
    )
    (net (code "113") (name "S10") (class "Default")
      (node (ref "IC1") (pin "23") (pinfunction "IO_L41N_GCLK26_3_23") (pintype "bidirectional"))
      (node (ref "TR10") (pin "3") (pinfunction "A_3") (pintype "bidirectional"))
    )
    (net (code "114") (name "S11") (class "Default")
      (node (ref "IC1") (pin "26") (pinfunction "IO_L37N_3_26") (pintype "bidirectional"))
      (node (ref "TR11") (pin "3") (pinfunction "A_3") (pintype "bidirectional"))
    )
    (net (code "115") (name "S12") (class "Default")
      (node (ref "IC1") (pin "29") (pinfunction "IO_L36N_3_29") (pintype "bidirectional"))
      (node (ref "TR12") (pin "3") (pinfunction "A_3") (pintype "bidirectional"))
    )
    (net (code "116") (name "S13") (class "Default")
      (node (ref "IC1") (pin "32") (pinfunction "IO_L2N_3_32") (pintype "bidirectional"))
      (node (ref "TR13") (pin "3") (pinfunction "A_3") (pintype "bidirectional"))
    )
    (net (code "117") (name "S14") (class "Default")
      (node (ref "IC1") (pin "34") (pinfunction "IO_L1N_VREF_3_34") (pintype "bidirectional"))
      (node (ref "TR14") (pin "3") (pinfunction "A_3") (pintype "bidirectional"))
    )
    (net (code "118") (name "S15") (class "Default")
      (node (ref "IC1") (pin "39") (pinfunction "IO_L65P_INIT_B_2_39") (pintype "bidirectional"))
      (node (ref "TR15") (pin "3") (pinfunction "A_3") (pintype "bidirectional"))
    )
    (net (code "119") (name "S16") (class "Default")
      (node (ref "IC1") (pin "41") (pinfunction "IO_L64P_D8_2_41") (pintype "bidirectional"))
      (node (ref "TR16") (pin "3") (pinfunction "A_3") (pintype "bidirectional"))
    )
    (net (code "120") (name "SD1") (class "Default")
      (node (ref "IC1") (pin "141") (pinfunction "IO_L2N_0_141") (pintype "bidirectional"))
      (node (ref "R43") (pin "2") (pinfunction "2_2") (pintype "passive"))
      (node (ref "TR1") (pin "5") (pinfunction "DIR_5") (pintype "input"))
    )
    (net (code "121") (name "SD2") (class "Default")
      (node (ref "IC1") (pin "143") (pinfunction "IO_L1N_VREF_0_143") (pintype "bidirectional"))
      (node (ref "R44") (pin "2") (pinfunction "2_2") (pintype "passive"))
      (node (ref "TR2") (pin "5") (pinfunction "DIR_5") (pintype "input"))
    )
    (net (code "122") (name "SD3") (class "Default")
      (node (ref "IC1") (pin "5") (pinfunction "IO_L52N_3_5") (pintype "bidirectional"))
      (node (ref "R45") (pin "2") (pinfunction "2_2") (pintype "passive"))
      (node (ref "TR3") (pin "5") (pinfunction "DIR_5") (pintype "input"))
    )
    (net (code "123") (name "SD4") (class "Default")
      (node (ref "IC1") (pin "7") (pinfunction "IO_L51N_3_7") (pintype "bidirectional"))
      (node (ref "R46") (pin "2") (pinfunction "2_2") (pintype "passive"))
      (node (ref "TR4") (pin "5") (pinfunction "DIR_5") (pintype "input"))
    )
    (net (code "124") (name "SD5") (class "Default")
      (node (ref "IC1") (pin "9") (pinfunction "IO_L50N_3_9") (pintype "bidirectional"))
      (node (ref "R47") (pin "2") (pinfunction "2_2") (pintype "passive"))
      (node (ref "TR5") (pin "5") (pinfunction "DIR_5") (pintype "input"))
    )
    (net (code "125") (name "SD6") (class "Default")
      (node (ref "IC1") (pin "11") (pinfunction "IO_L49N_3_11") (pintype "bidirectional"))
      (node (ref "R48") (pin "2") (pinfunction "2_2") (pintype "passive"))
      (node (ref "TR6") (pin "5") (pinfunction "DIR_5") (pintype "input"))
    )
    (net (code "126") (name "SD7") (class "Default")
      (node (ref "IC1") (pin "14") (pinfunction "IO_L44N_GCLK20_3_14") (pintype "bidirectional"))
      (node (ref "R49") (pin "2") (pinfunction "2_2") (pintype "passive"))
      (node (ref "TR7") (pin "5") (pinfunction "DIR_5") (pintype "input"))
    )
    (net (code "127") (name "SD8") (class "Default")
      (node (ref "IC1") (pin "16") (pinfunction "IO_L43N_GCLK22_IRDY2_3_16") (pintype "bidirectional"))
      (node (ref "R50") (pin "2") (pinfunction "2_2") (pintype "passive"))
      (node (ref "TR8") (pin "5") (pinfunction "DIR_5") (pintype "input"))
    )
    (net (code "128") (name "SD9") (class "Default")
      (node (ref "IC1") (pin "22") (pinfunction "IO_L42P_GCLK25_TRDY2_3_22") (pintype "bidirectional"))
      (node (ref "R51") (pin "2") (pinfunction "2_2") (pintype "passive"))
      (node (ref "TR9") (pin "5") (pinfunction "DIR_5") (pintype "input"))
    )
    (net (code "129") (name "SD10") (class "Default")
      (node (ref "IC1") (pin "24") (pinfunction "IO_L41P_GCLK27_3_24") (pintype "bidirectional"))
      (node (ref "R52") (pin "2") (pinfunction "2_2") (pintype "passive"))
      (node (ref "TR10") (pin "5") (pinfunction "DIR_5") (pintype "input"))
    )
    (net (code "130") (name "SD11") (class "Default")
      (node (ref "IC1") (pin "27") (pinfunction "IO_L37P_3_27") (pintype "bidirectional"))
      (node (ref "R53") (pin "2") (pinfunction "2_2") (pintype "passive"))
      (node (ref "TR11") (pin "5") (pinfunction "DIR_5") (pintype "input"))
    )
    (net (code "131") (name "SD12") (class "Default")
      (node (ref "IC1") (pin "30") (pinfunction "IO_L36P_3_30") (pintype "bidirectional"))
      (node (ref "R54") (pin "2") (pinfunction "2_2") (pintype "passive"))
      (node (ref "TR12") (pin "5") (pinfunction "DIR_5") (pintype "input"))
    )
    (net (code "132") (name "SD13") (class "Default")
      (node (ref "IC1") (pin "33") (pinfunction "IO_L2P_3_33") (pintype "bidirectional"))
      (node (ref "R55") (pin "2") (pinfunction "2_2") (pintype "passive"))
      (node (ref "TR13") (pin "5") (pinfunction "DIR_5") (pintype "input"))
    )
    (net (code "133") (name "SD14") (class "Default")
      (node (ref "IC1") (pin "35") (pinfunction "IO_L1P_3_35") (pintype "bidirectional"))
      (node (ref "R56") (pin "2") (pinfunction "2_2") (pintype "passive"))
      (node (ref "TR14") (pin "5") (pinfunction "DIR_5") (pintype "input"))
    )
    (net (code "134") (name "SD15") (class "Default")
      (node (ref "IC1") (pin "40") (pinfunction "IO_L64N_D9_2_40") (pintype "bidirectional"))
      (node (ref "R57") (pin "2") (pinfunction "2_2") (pintype "passive"))
      (node (ref "TR15") (pin "5") (pinfunction "DIR_5") (pintype "input"))
    )
    (net (code "135") (name "SD16") (class "Default")
      (node (ref "IC1") (pin "43") (pinfunction "IO_L62N_D6_2_43") (pintype "bidirectional"))
      (node (ref "R58") (pin "2") (pinfunction "2_2") (pintype "passive"))
      (node (ref "TR16") (pin "5") (pinfunction "DIR_5") (pintype "input"))
    )
    (net (code "136") (name "TCK") (class "Default")
      (node (ref "IC1") (pin "109") (pinfunction "TCK_109") (pintype "input"))
      (node (ref "TP14") (pin "TP") (pinfunction "TP_TP") (pintype "input"))
    )
    (net (code "137") (name "TDI") (class "Default")
      (node (ref "IC1") (pin "110") (pinfunction "TDI_110") (pintype "input"))
      (node (ref "TP15") (pin "TP") (pinfunction "TP_TP") (pintype "input"))
    )
    (net (code "138") (name "TDO") (class "Default")
      (node (ref "IC1") (pin "106") (pinfunction "TDO_106") (pintype "output"))
      (node (ref "TP16") (pin "TP") (pinfunction "TP_TP") (pintype "input"))
    )
    (net (code "139") (name "TMS") (class "Default")
      (node (ref "IC1") (pin "107") (pinfunction "TMS_107") (pintype "input"))
      (node (ref "TP13") (pin "TP") (pinfunction "TP_TP") (pintype "input"))
    )
    (net (code "140") (name "USB_D+") (class "Default")
      (node (ref "IC1") (pin "59") (pinfunction "IO_L13N_D10_2_59") (pintype "bidirectional"))
      (node (ref "R2") (pin "2") (pinfunction "2_2") (pintype "passive"))
    )
    (net (code "141") (name "USB_D-") (class "Default")
      (node (ref "IC1") (pin "56") (pinfunction "IO_L30P_GCLK1_D13_2_56") (pintype "bidirectional"))
      (node (ref "R1") (pin "2") (pinfunction "2_2") (pintype "passive"))
    )
    (net (code "142") (name "USB_PUP") (class "Default")
      (node (ref "IC1") (pin "67") (pinfunction "IO_L2P_CMPCLK_2_67") (pintype "bidirectional"))
      (node (ref "R3") (pin "2") (pinfunction "2_2") (pintype "passive"))
    )
    (net (code "143") (name "USB_S+") (class "Default")
      (node (ref "IC1") (pin "58") (pinfunction "IO_L14P_D11_2_58") (pintype "bidirectional"))
      (node (ref "R2") (pin "1") (pinfunction "1_1") (pintype "passive"))
      (node (ref "R3") (pin "1") (pinfunction "1_1") (pintype "passive"))
      (node (ref "X1") (pin "3") (pinfunction "D+_3") (pintype "bidirectional"))
    )
    (net (code "144") (name "USB_S-") (class "Default")
      (node (ref "IC1") (pin "57") (pinfunction "IO_L14N_D12_2_57") (pintype "bidirectional"))
      (node (ref "R1") (pin "1") (pinfunction "1_1") (pintype "passive"))
      (node (ref "X1") (pin "2") (pinfunction "D-_2") (pintype "bidirectional"))
    )
    (net (code "145") (name "VCCINT") (class "Default")
      (node (ref "C18") (pin "1") (pinfunction "1_1") (pintype "passive"))
      (node (ref "C19") (pin "1") (pinfunction "1_1") (pintype "passive"))
      (node (ref "C20") (pin "1") (pinfunction "1_1") (pintype "passive"))
      (node (ref "IC1") (pin "128") (pinfunction "VCCINT_128") (pintype "power_in"))
      (node (ref "IC1") (pin "19") (pinfunction "VCCINT_19") (pintype "power_in"))
      (node (ref "IC1") (pin "28") (pinfunction "VCCINT_28") (pintype "power_in"))
      (node (ref "IC1") (pin "52") (pinfunction "VCCINT_52") (pintype "power_in"))
      (node (ref "IC1") (pin "89") (pinfunction "VCCINT_89") (pintype "power_in"))
      (node (ref "L1") (pin "2") (pinfunction "2_2") (pintype "passive"))
    )
    (net (code "146") (name "VCCIO") (class "Default")
      (node (ref "C10") (pin "1") (pinfunction "1_1") (pintype "passive"))
      (node (ref "C11") (pin "1") (pinfunction "1_1") (pintype "passive"))
      (node (ref "C12") (pin "1") (pinfunction "1_1") (pintype "passive"))
      (node (ref "C3") (pin "1") (pinfunction "1_1") (pintype "passive"))
      (node (ref "C4") (pin "1") (pinfunction "1_1") (pintype "passive"))
      (node (ref "C7") (pin "1") (pinfunction "1_1") (pintype "passive"))
      (node (ref "C8") (pin "1") (pinfunction "1_1") (pintype "passive"))
      (node (ref "C9") (pin "1") (pinfunction "1_1") (pintype "passive"))
      (node (ref "IC1") (pin "129") (pinfunction "VCCAUX_129") (pintype "power_in"))
      (node (ref "IC1") (pin "20") (pinfunction "VCCAUX_20") (pintype "power_in"))
      (node (ref "IC1") (pin "36") (pinfunction "VCCAUX_36") (pintype "power_in"))
      (node (ref "IC1") (pin "53") (pinfunction "VCCAUX_53") (pintype "power_in"))
      (node (ref "IC1") (pin "90") (pinfunction "VCCAUX_90") (pintype "power_in"))
      (node (ref "L2") (pin "2") (pinfunction "2_2") (pintype "passive"))
    )
    (net (code "147") (name "VCC_B1") (class "Default")
      (node (ref "C34") (pin "1") (pinfunction "1_1") (pintype "passive"))
      (node (ref "JP3") (pin "1") (pinfunction "1_1") (pintype "passive"))
      (node (ref "JP4") (pin "1") (pinfunction "1_1") (pintype "passive"))
      (node (ref "TR1") (pin "6") (pinfunction "VCCB_6") (pintype "passive"))
      (node (ref "TR2") (pin "6") (pinfunction "VCCB_6") (pintype "passive"))
      (node (ref "TR3") (pin "6") (pinfunction "VCCB_6") (pintype "passive"))
      (node (ref "TR4") (pin "6") (pinfunction "VCCB_6") (pintype "passive"))
      (node (ref "TR5") (pin "6") (pinfunction "VCCB_6") (pintype "passive"))
      (node (ref "TR6") (pin "6") (pinfunction "VCCB_6") (pintype "passive"))
      (node (ref "TR7") (pin "6") (pinfunction "VCCB_6") (pintype "passive"))
      (node (ref "TR8") (pin "6") (pinfunction "VCCB_6") (pintype "passive"))
    )
    (net (code "148") (name "VCC_B2") (class "Default")
      (node (ref "C35") (pin "1") (pinfunction "1_1") (pintype "passive"))
      (node (ref "JP1") (pin "1") (pinfunction "1_1") (pintype "passive"))
      (node (ref "JP2") (pin "1") (pinfunction "1_1") (pintype "passive"))
      (node (ref "Q2") (pin "3") (pinfunction "C_3") (pintype "passive"))
      (node (ref "Q4") (pin "3") (pinfunction "C_3") (pintype "passive"))
      (node (ref "R63") (pin "1") (pinfunction "1_1") (pintype "passive"))
      (node (ref "TR10") (pin "6") (pinfunction "VCCB_6") (pintype "passive"))
      (node (ref "TR11") (pin "6") (pinfunction "VCCB_6") (pintype "passive"))
      (node (ref "TR12") (pin "6") (pinfunction "VCCB_6") (pintype "passive"))
      (node (ref "TR13") (pin "6") (pinfunction "VCCB_6") (pintype "passive"))
      (node (ref "TR14") (pin "6") (pinfunction "VCCB_6") (pintype "passive"))
      (node (ref "TR15") (pin "6") (pinfunction "VCCB_6") (pintype "passive"))
      (node (ref "TR16") (pin "6") (pinfunction "VCCB_6") (pintype "passive"))
      (node (ref "TR9") (pin "6") (pinfunction "VCCB_6") (pintype "passive"))
    )
    (net (code "149") (name "VIO33") (class "Default")
      (node (ref "IC1") (pin "44") (pinfunction "IO_L62P_D5_2_44") (pintype "bidirectional"))
      (node (ref "Q3") (pin "1") (pinfunction "B_1") (pintype "passive"))
    )
    (net (code "150") (name "VIO50") (class "Default")
      (node (ref "IC1") (pin "45") (pinfunction "IO_L49N_D4_2_45") (pintype "bidirectional"))
      (node (ref "Q1") (pin "1") (pinfunction "B_1") (pintype "passive"))
    )
    (net (code "151") (name "unconnected-(IC1-CMPCS_B_2-Pad72)") (class "Default")
      (node (ref "IC1") (pin "72") (pinfunction "CMPCS_B_2_72") (pintype "bidirectional"))
    )
    (net (code "152") (name "unconnected-(IC1-IO_L2N_CMPMOSI_2-Pad66)") (class "Default")
      (node (ref "IC1") (pin "66") (pinfunction "IO_L2N_CMPMOSI_2_66") (pintype "bidirectional"))
    )
    (net (code "153") (name "unconnected-(IC1-IO_L4N_0-Pad137)") (class "Default")
      (node (ref "IC1") (pin "137") (pinfunction "IO_L4N_0_137") (pintype "bidirectional"))
    )
    (net (code "154") (name "unconnected-(IC1-IO_L12N_D2_MISO3_2-Pad61)") (class "Default")
      (node (ref "IC1") (pin "61") (pinfunction "IO_L12N_D2_MISO3_2_61") (pintype "bidirectional"))
    )
    (net (code "155") (name "unconnected-(IC1-IO_L12P_D1_MISO2_2-Pad62)") (class "Default")
      (node (ref "IC1") (pin "62") (pinfunction "IO_L12P_D1_MISO2_2_62") (pintype "bidirectional"))
    )
    (net (code "156") (name "unconnected-(IC1-IO_L30N_GCLK0_USERCCLK_2-Pad55)") (class "Default")
      (node (ref "IC1") (pin "55") (pinfunction "IO_L30N_GCLK0_USERCCLK_2_55") (pintype "bidirectional"))
    )
    (net (code "157") (name "unconnected-(IC1-IO_L31N_GCLK30_D15_2-Pad50)") (class "Default")
      (node (ref "IC1") (pin "50") (pinfunction "IO_L31N_GCLK30_D15_2_50") (pintype "bidirectional"))
    )
    (net (code "158") (name "unconnected-(IC1-IO_L43P_GCLK23_3-Pad17)") (class "Default")
      (node (ref "IC1") (pin "17") (pinfunction "IO_L43P_GCLK23_3_17") (pintype "bidirectional"))
    )
    (net (code "159") (name "unconnected-(IC1-IO_L48P_D7_2-Pad48)") (class "Default")
      (node (ref "IC1") (pin "48") (pinfunction "IO_L48P_D7_2_48") (pintype "bidirectional"))
    )
    (net (code "160") (name "unconnected-(IC1-IO_L83N_VREF_3-Pad1)") (class "Default")
      (node (ref "IC1") (pin "1") (pinfunction "IO_L83N_VREF_3_1") (pintype "bidirectional"))
    )
    (net (code "161") (name "unconnected-(IC3-NC-Pad4)") (class "Default")
      (node (ref "IC3") (pin "4") (pinfunction "NC_4") (pintype "no_connect"))
    )
    (net (code "162") (name "unconnected-(IC4A-NC-Pad40)") (class "Default")
      (node (ref "IC4") (pin "40") (pinfunction "NC_40") (pintype "no_connect"))
    )
  )
)
